# mk312lite_V4a.net
KiCad netlist of a schematic drawn in EAGLE
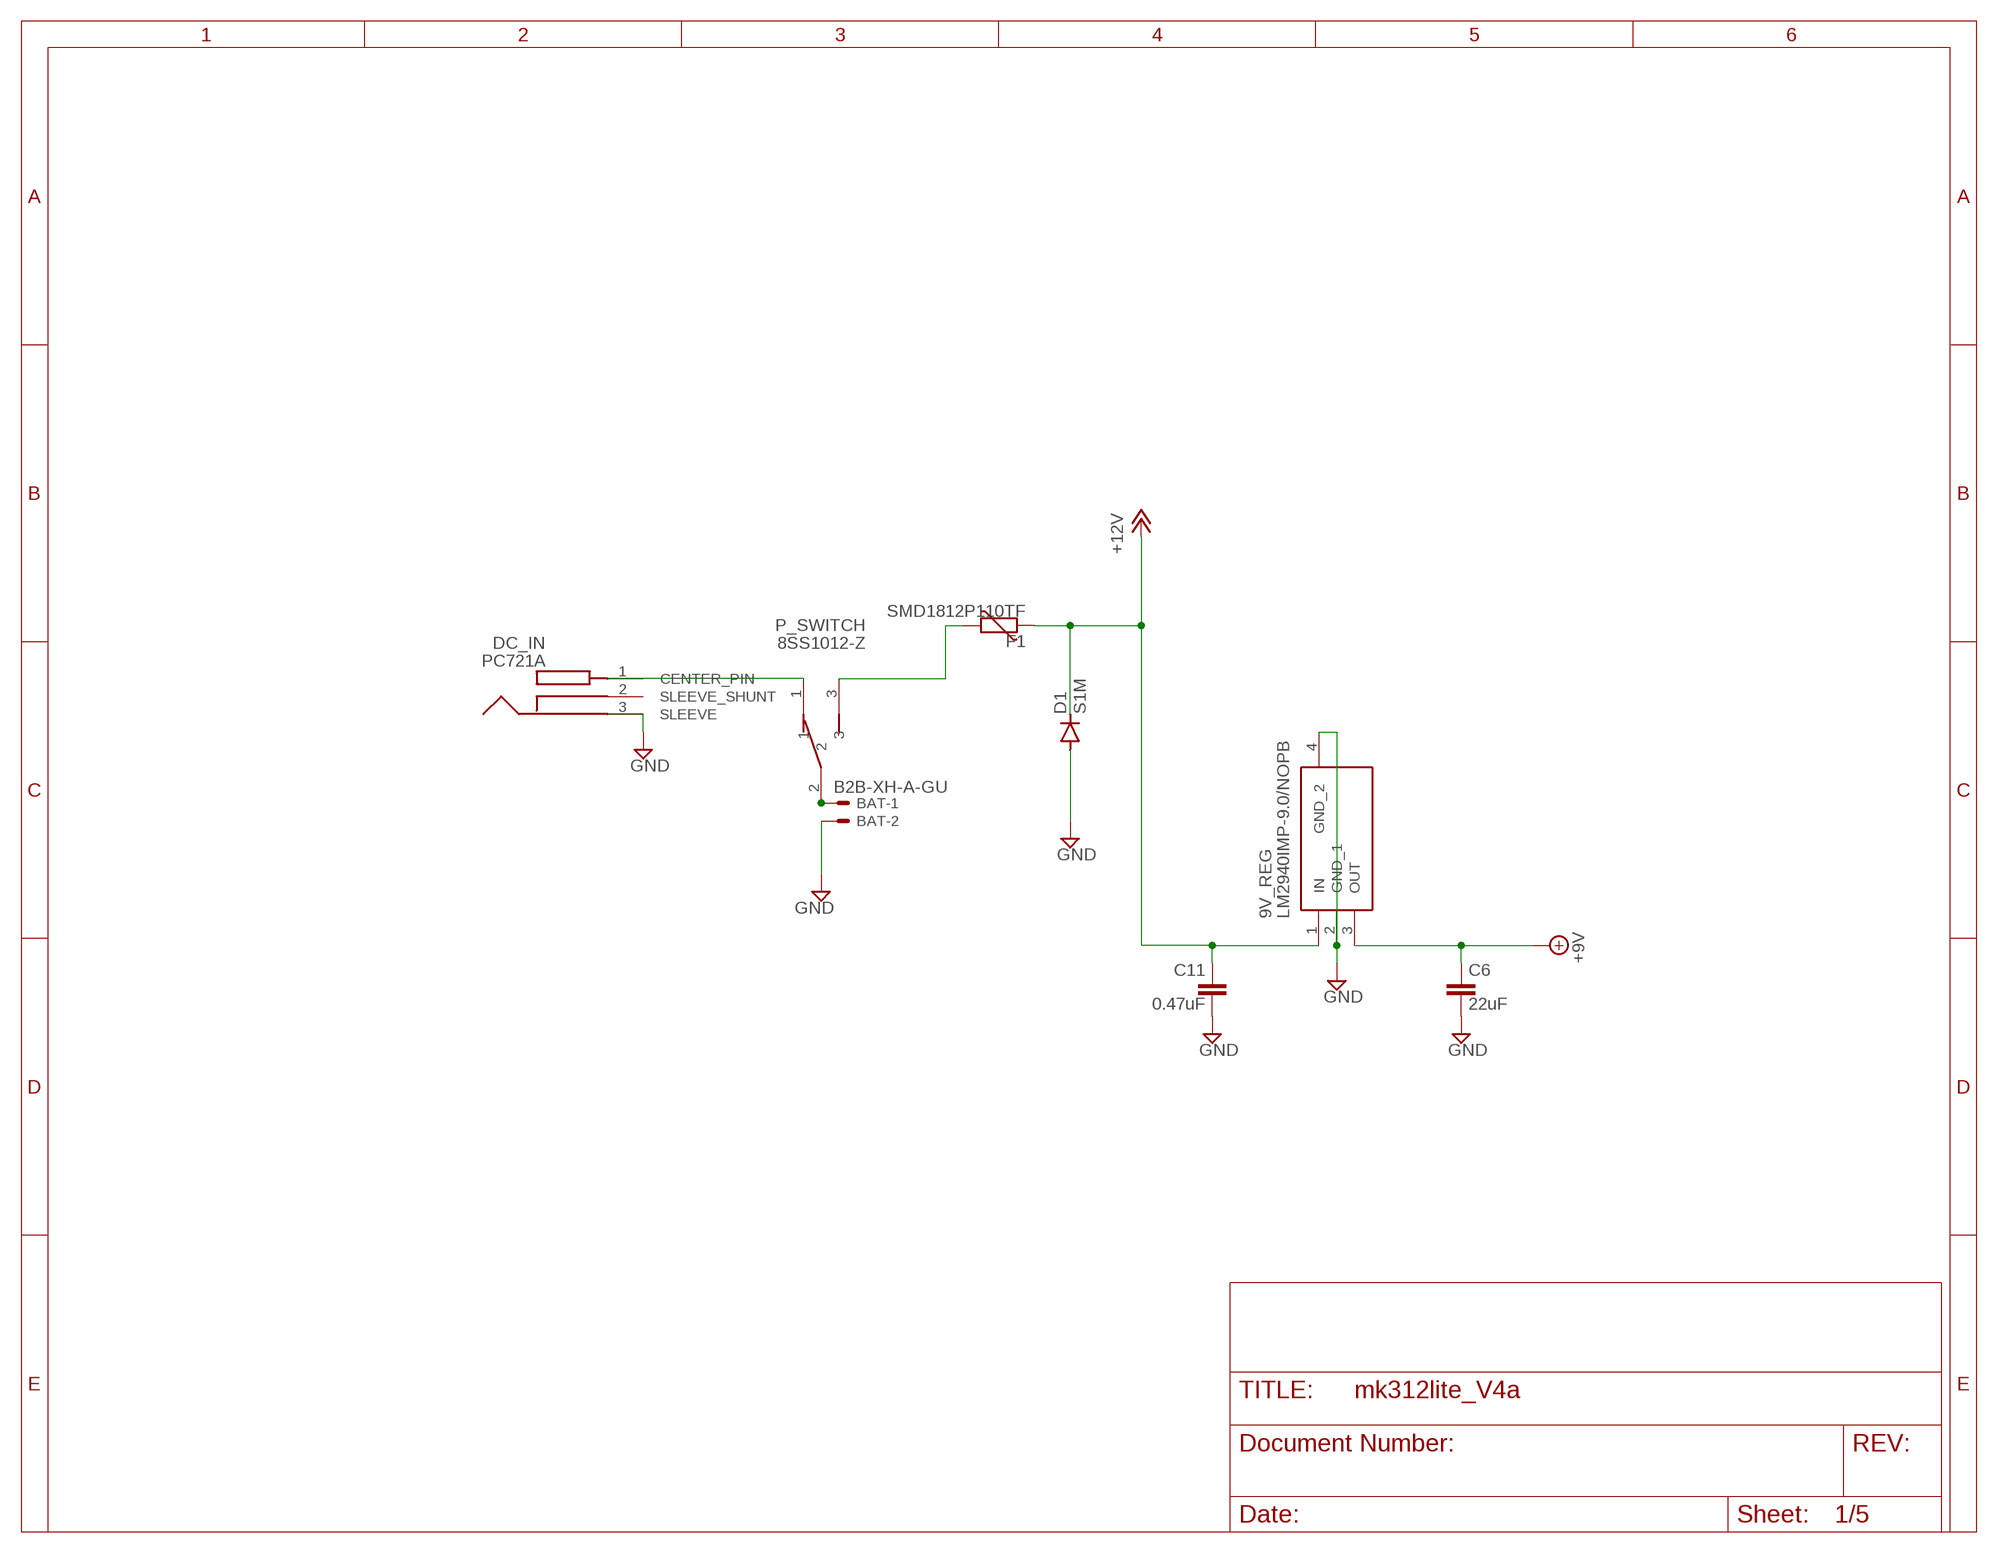
[diagram p0: schematic, sheet 1]
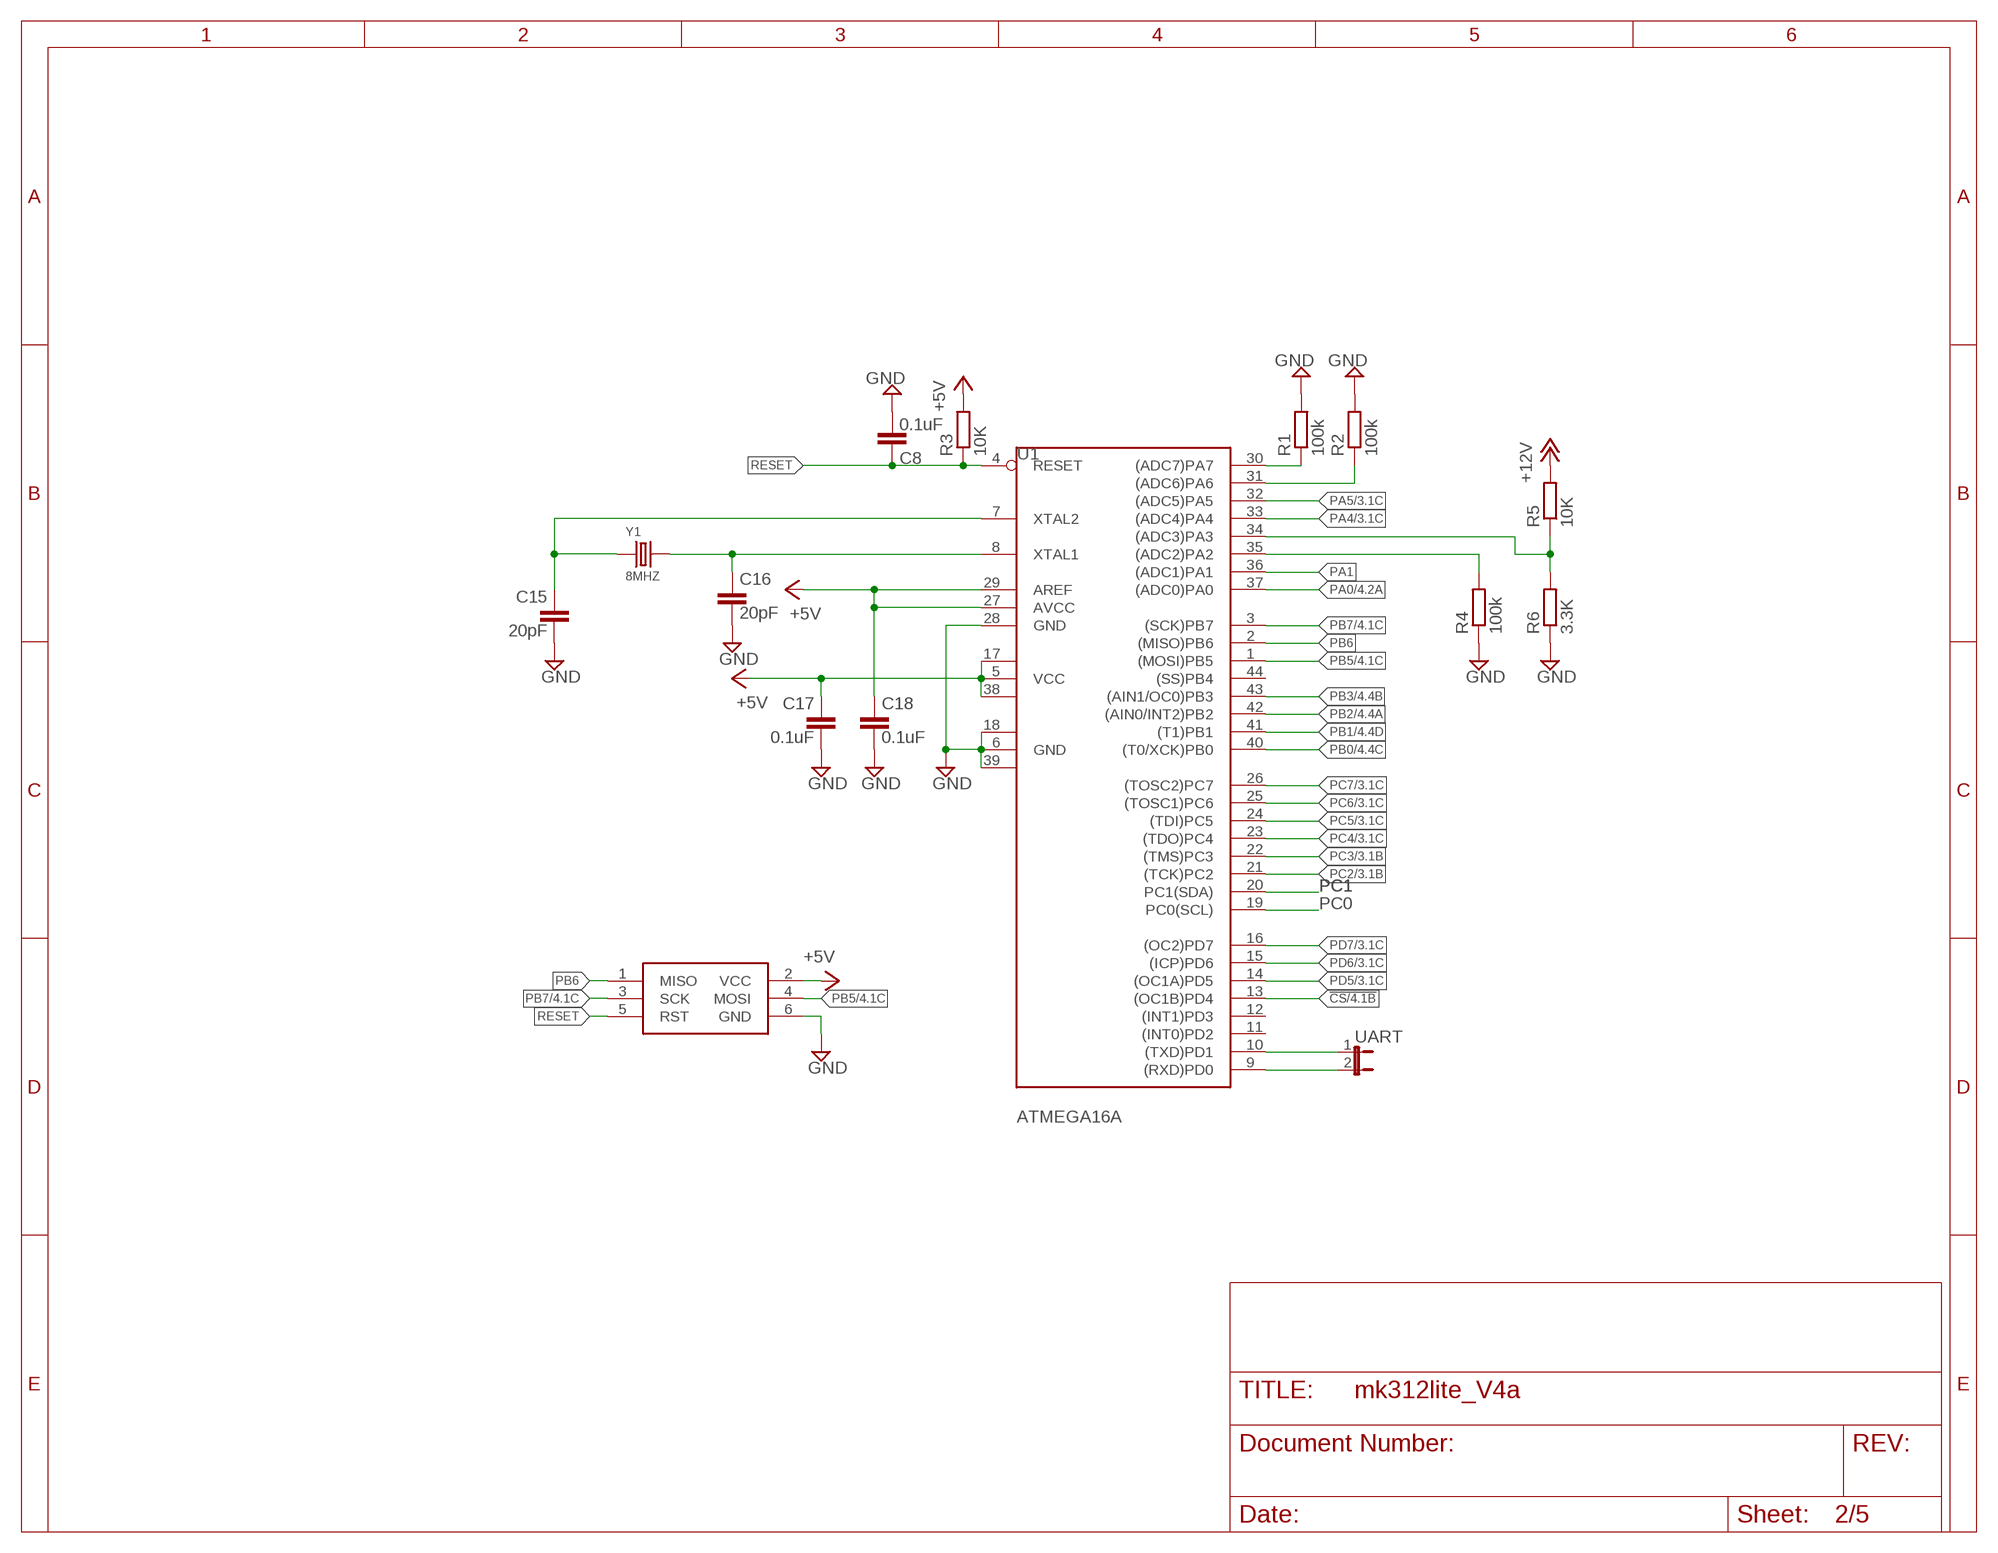
[diagram p1: schematic, sheet 2]
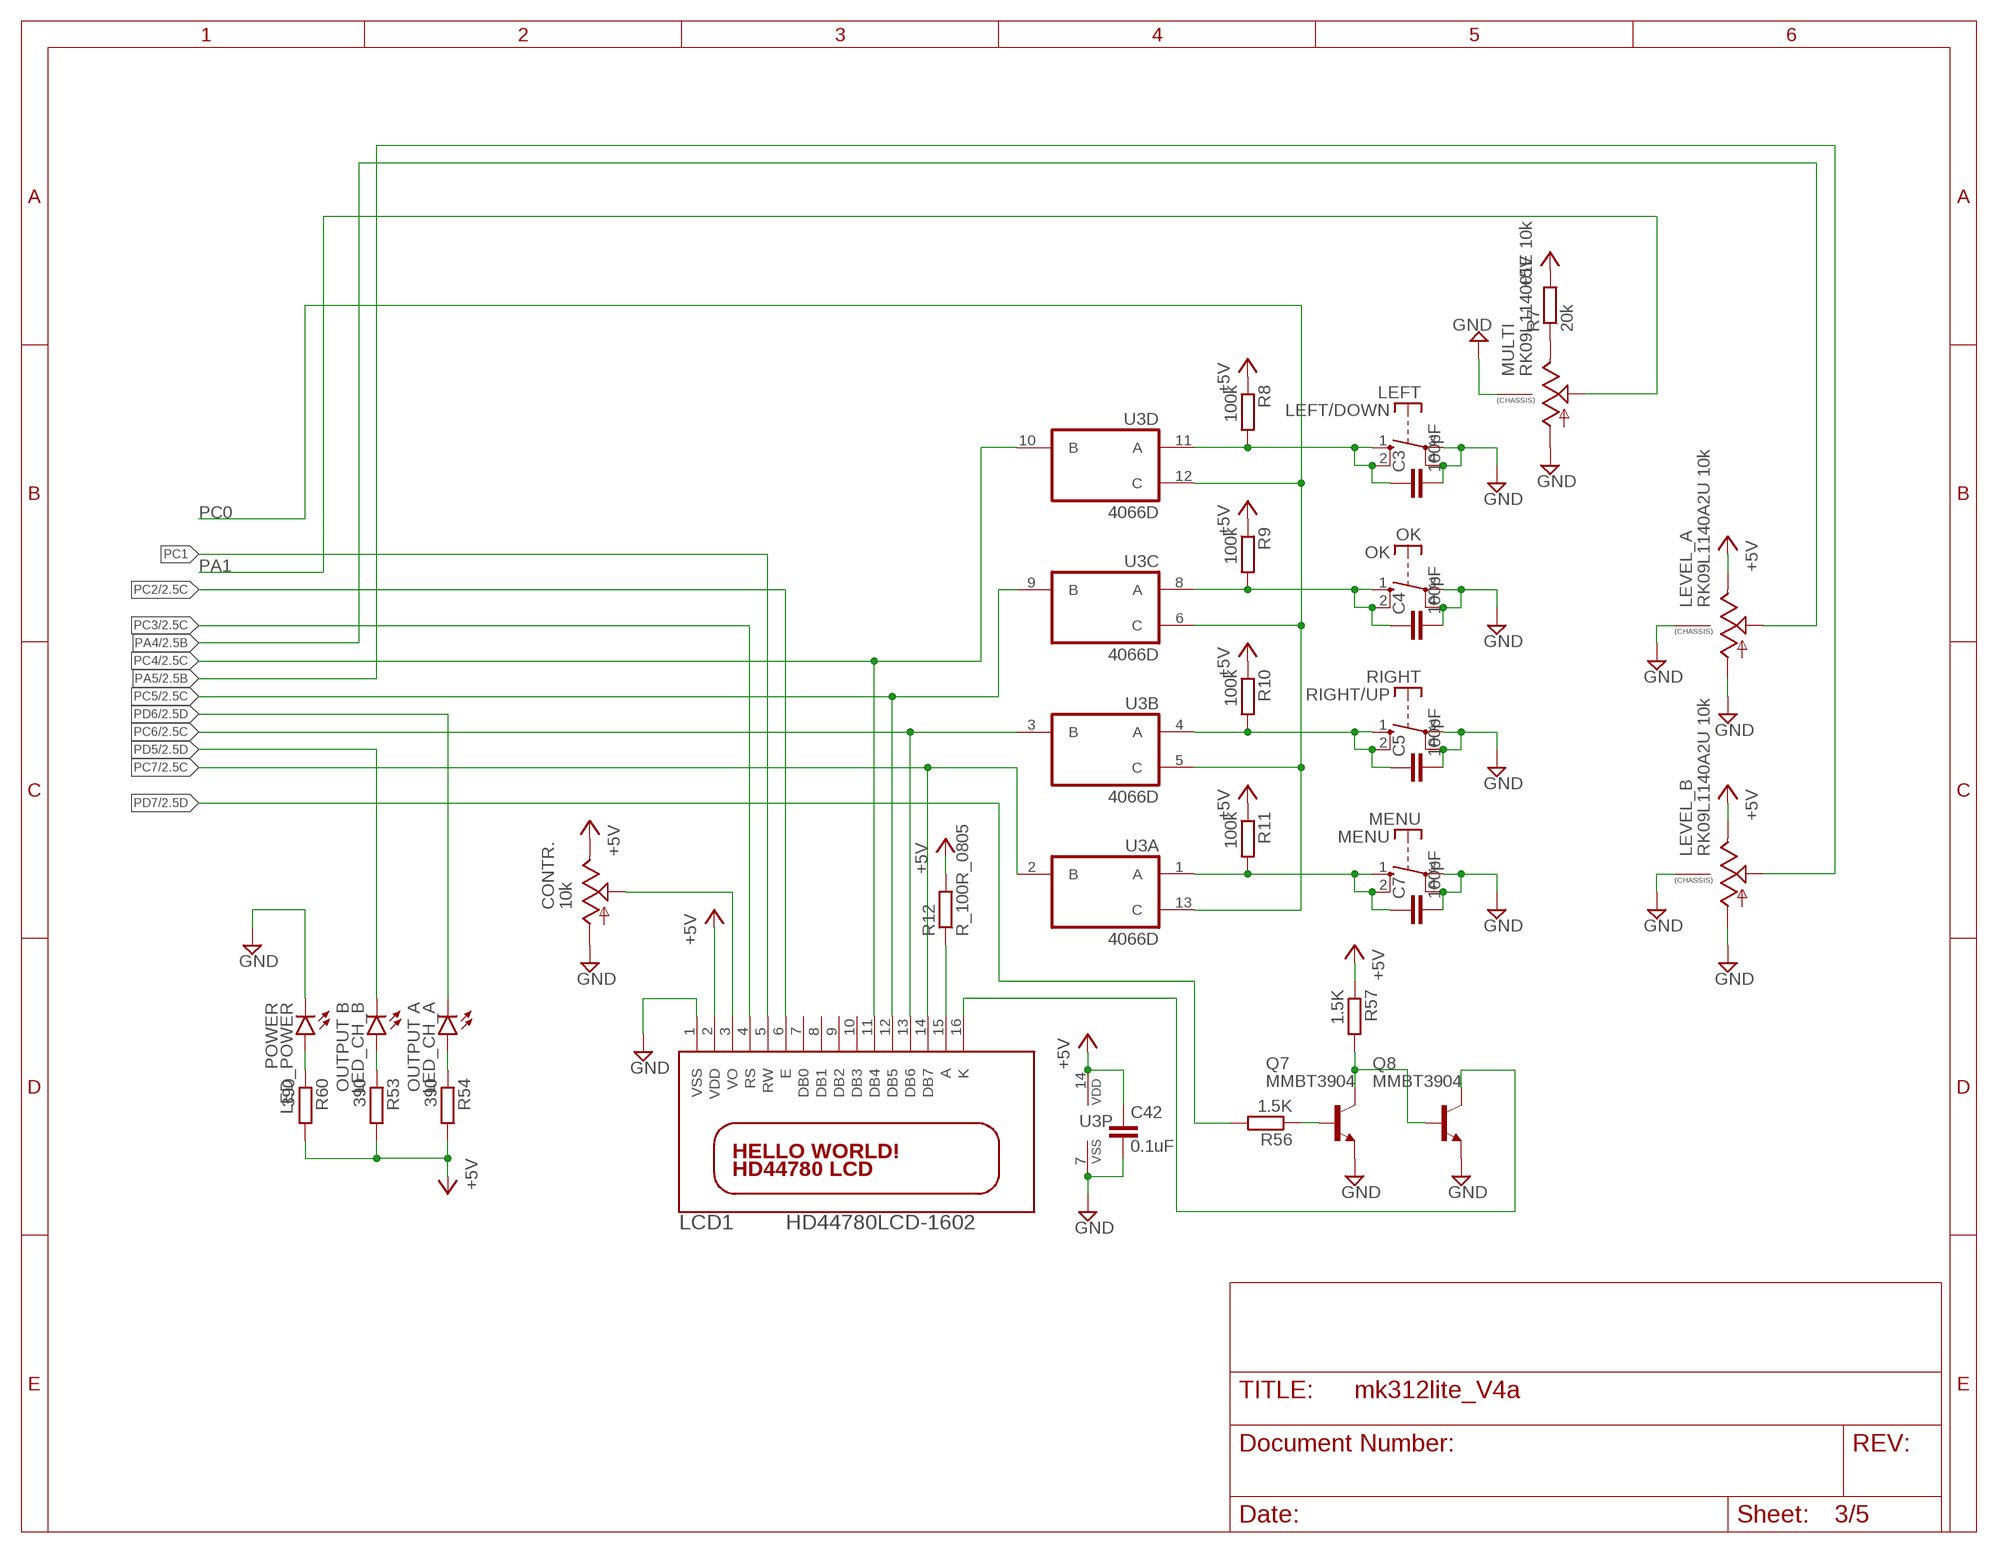
[diagram p2: schematic, sheet 3]
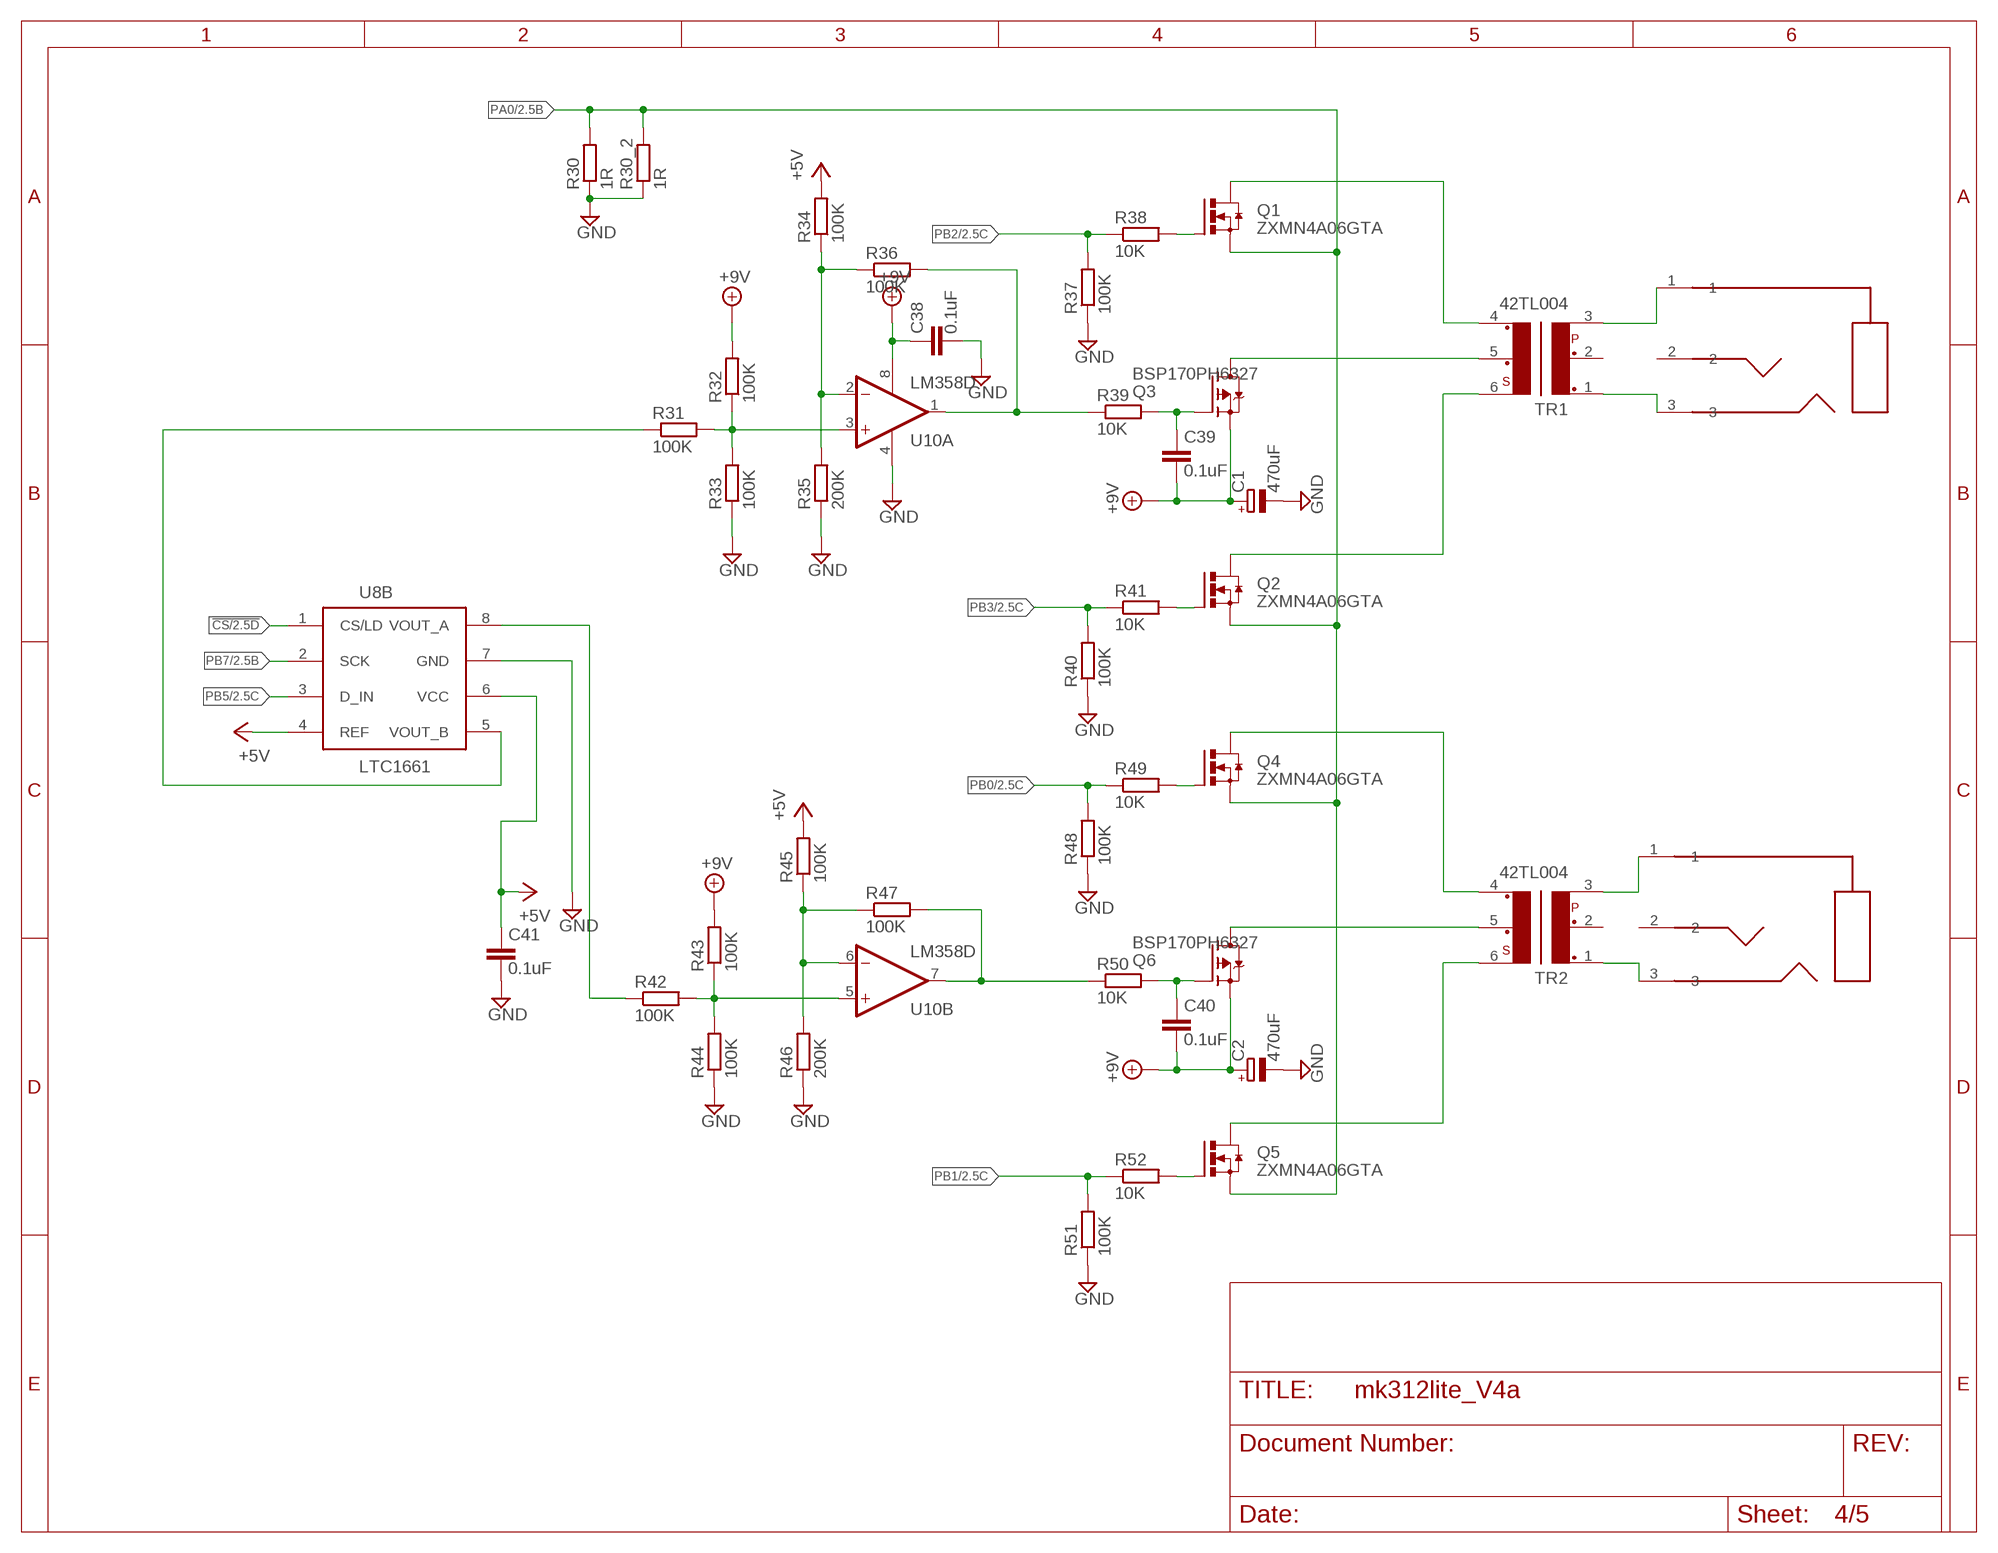
[diagram p3: schematic, sheet 4]
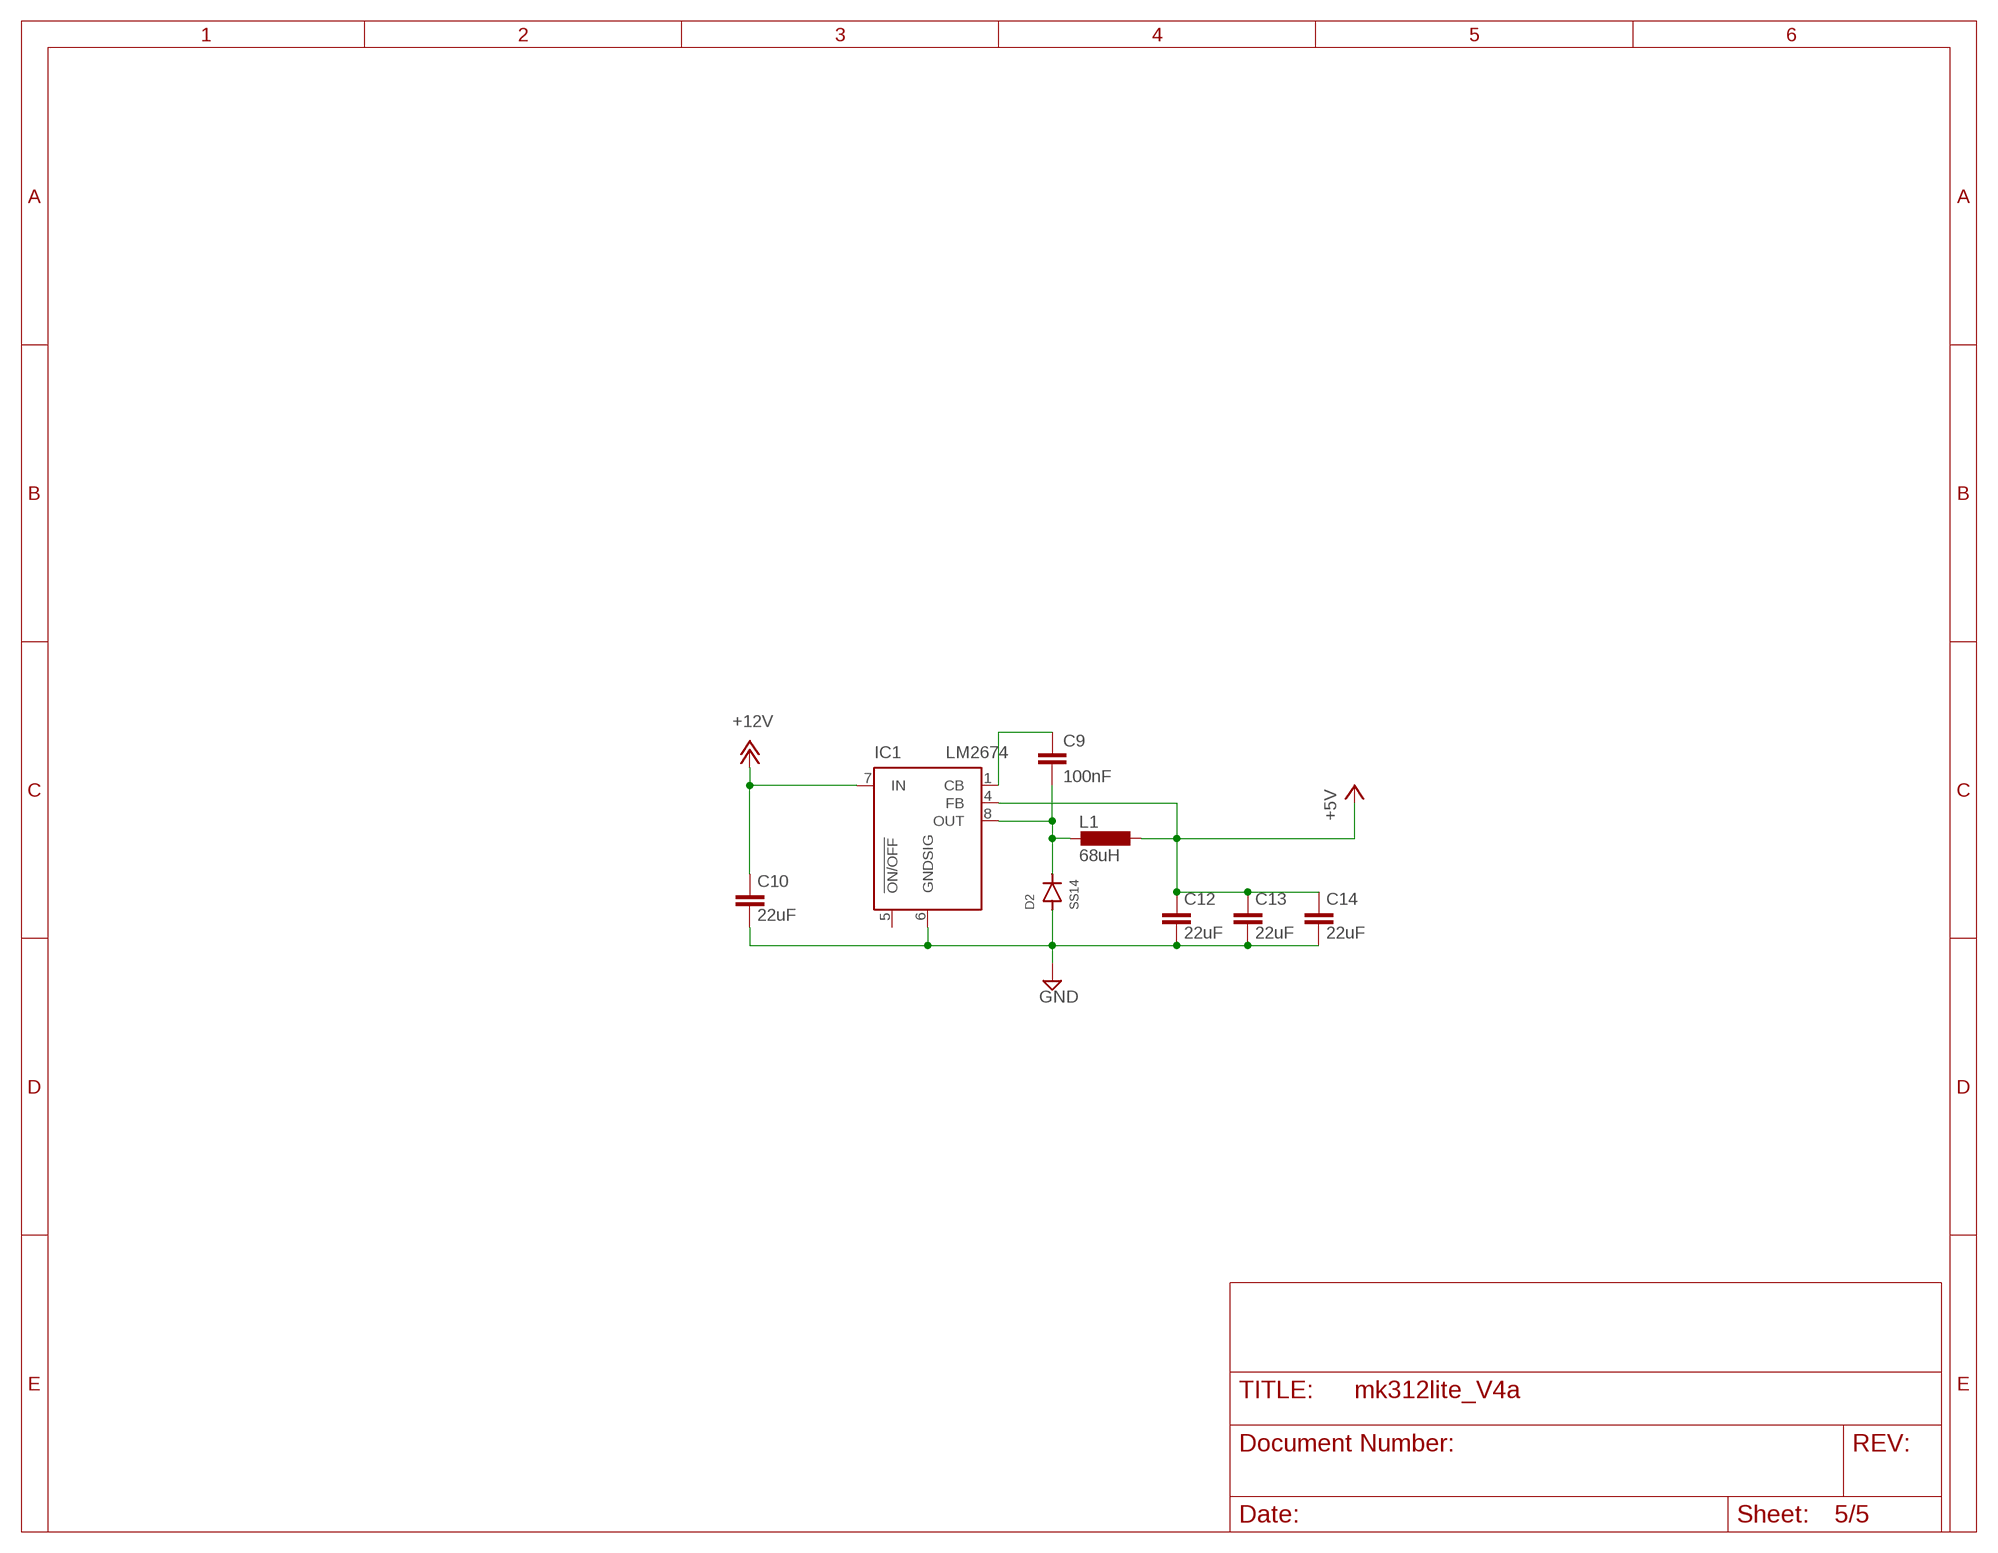
[diagram p4: schematic, sheet 5]

(export (version "E")
  (design (tool "Eeschema 10.0.6"))
  (components
    (comp (ref "C8")
      (value "0.1uF")
      (footprint "eagle-import:C0805")
      (libsource (lib "eagle-import") (part "C-EUC0805"))
    )
    (comp (ref "C15")
      (value "20pF")
      (footprint "eagle-import:C0603")
      (libsource (lib "eagle-import") (part "C-EUC0603"))
    )
    (comp (ref "C16")
      (value "20pF")
      (footprint "eagle-import:C0603")
      (libsource (lib "eagle-import") (part "C-EUC0603"))
    )
    (comp (ref "C17")
      (value "0.1uF")
      (footprint "eagle-import:C0805")
      (libsource (lib "eagle-import") (part "C-EUC0805"))
    )
    (comp (ref "C18")
      (value "0.1uF")
      (footprint "eagle-import:C0805")
      (libsource (lib "eagle-import") (part "C-EUC0805"))
    )
    (comp (ref "ISP1")
      (value "AVRISP-6")
      (footprint "eagle-import:AVRISP")
      (libsource (lib "eagle-import") (part "AVRISP-6"))
    )
    (comp (ref "R1")
      (value "100k")
      (footprint "eagle-import:R0805")
      (libsource (lib "eagle-import") (part "R-EU_R0805"))
    )
    (comp (ref "R2")
      (value "100k")
      (footprint "eagle-import:R0805")
      (libsource (lib "eagle-import") (part "R-EU_R0805"))
    )
    (comp (ref "R3")
      (value "10K")
      (footprint "eagle-import:R0805")
      (libsource (lib "eagle-import") (part "R-EU_R0805"))
    )
    (comp (ref "R4")
      (value "100k")
      (footprint "eagle-import:R0805")
      (libsource (lib "eagle-import") (part "R-EU_R0805"))
    )
    (comp (ref "R5")
      (value "10K")
      (footprint "eagle-import:R0805")
      (libsource (lib "eagle-import") (part "R-EU_R0805"))
    )
    (comp (ref "R6")
      (value "3.3K")
      (footprint "eagle-import:R0805")
      (libsource (lib "eagle-import") (part "R-EU_R0805"))
    )
    (comp (ref "U1")
      (value "ATMEGA16A")
      (footprint "eagle-import:TQFP44")
      (fields (field (name "MPN") "ATMEGA16-16AU"))
      (libsource (lib "eagle-import") (part "MEGA16-A"))
    )
    (comp (ref "UART")
      (value "JP1E")
      (footprint "eagle-import:JP1")
      (libsource (lib "eagle-import") (part "JP1E"))
    )
    (comp (ref "Y1")
      (value "8MHZ")
      (footprint "eagle-import:X2-SMD-5.0X3.2X1.3MM")
      (fields (field (name "MPN") "5032/2P"))
      (libsource (lib "eagle-import") (part "SMD-CRYSTAL-8MHZ-20PF-20PPM(2P-5.0X3.2MM)"))
    )
    (comp (ref "C1")
      (value "470uF")
      (footprint "eagle-import:150CLZ-1010")
      (libsource (lib "eagle-import") (part "CPOL-EU150CLZ-1010"))
    )
    (comp (ref "C2")
      (value "470uF")
      (footprint "eagle-import:150CLZ-1010")
      (libsource (lib "eagle-import") (part "CPOL-EU150CLZ-1010"))
    )
    (comp (ref "C38")
      (value "0.1uF")
      (footprint "eagle-import:C0805")
      (libsource (lib "eagle-import") (part "C-EUC0805"))
    )
    (comp (ref "C39")
      (value "0.1uF")
      (footprint "eagle-import:C0805")
      (libsource (lib "eagle-import") (part "C-EUC0805"))
    )
    (comp (ref "C40")
      (value "0.1uF")
      (footprint "eagle-import:C0805")
      (libsource (lib "eagle-import") (part "C-EUC0805"))
    )
    (comp (ref "C41")
      (value "0.1uF")
      (footprint "eagle-import:C0805")
      (libsource (lib "eagle-import") (part "C-EUC0805"))
    )
    (comp (ref "CHAN_A")
      (value "PJ-301C")
      (footprint "eagle-import:PJ-301C")
      (libsource (lib "eagle-import") (part "PC-301C"))
    )
    (comp (ref "CHAN_B")
      (value "PJ-301C")
      (footprint "eagle-import:PJ-301C")
      (libsource (lib "eagle-import") (part "PC-301C"))
    )
    (comp (ref "Q1")
      (value "ZXMN4A06GTA")
      (footprint "eagle-import:SOT223")
      (libsource (lib "eagle-import") (part "N-HEXFET-2D_?-SOT232IRLL2705"))
    )
    (comp (ref "Q2")
      (value "ZXMN4A06GTA")
      (footprint "eagle-import:SOT223")
      (libsource (lib "eagle-import") (part "N-HEXFET-2D_?-SOT232IRLL2705"))
    )
    (comp (ref "Q3")
      (value "BSP170PH6327")
      (footprint "eagle-import:SOT230P700X180-4N")
      (libsource (lib "eagle-import") (part "IRFL9014TRPBF"))
    )
    (comp (ref "Q4")
      (value "ZXMN4A06GTA")
      (footprint "eagle-import:SOT223")
      (libsource (lib "eagle-import") (part "N-HEXFET-2D_?-SOT232IRLL2705"))
    )
    (comp (ref "Q5")
      (value "ZXMN4A06GTA")
      (footprint "eagle-import:SOT223")
      (libsource (lib "eagle-import") (part "N-HEXFET-2D_?-SOT232IRLL2705"))
    )
    (comp (ref "Q6")
      (value "BSP170PH6327")
      (footprint "eagle-import:SOT230P700X180-4N")
      (libsource (lib "eagle-import") (part "IRFL9014TRPBF"))
    )
    (comp (ref "R30")
      (value "1R")
      (footprint "eagle-import:R1206")
      (libsource (lib "eagle-import") (part "R-EU_R1206"))
    )
    (comp (ref "R30_2")
      (value "1R")
      (footprint "eagle-import:R1206")
      (libsource (lib "eagle-import") (part "R-EU_R1206"))
    )
    (comp (ref "R31")
      (value "100K")
      (footprint "eagle-import:R0805")
      (libsource (lib "eagle-import") (part "R-EU_R0805"))
    )
    (comp (ref "R32")
      (value "100K")
      (footprint "eagle-import:R0805")
      (libsource (lib "eagle-import") (part "R-EU_R0805"))
    )
    (comp (ref "R33")
      (value "100K")
      (footprint "eagle-import:R0805")
      (libsource (lib "eagle-import") (part "R-EU_R0805"))
    )
    (comp (ref "R34")
      (value "100K")
      (footprint "eagle-import:R0805")
      (libsource (lib "eagle-import") (part "R-EU_R0805"))
    )
    (comp (ref "R35")
      (value "200K")
      (footprint "eagle-import:R0805")
      (libsource (lib "eagle-import") (part "R-EU_R0805"))
    )
    (comp (ref "R36")
      (value "100K")
      (footprint "eagle-import:R0805")
      (libsource (lib "eagle-import") (part "R-EU_R0805"))
    )
    (comp (ref "R37")
      (value "100K")
      (footprint "eagle-import:R0805")
      (libsource (lib "eagle-import") (part "R-EU_R0805"))
    )
    (comp (ref "R38")
      (value "10K")
      (footprint "eagle-import:R0805")
      (libsource (lib "eagle-import") (part "R-EU_R0805"))
    )
    (comp (ref "R39")
      (value "10K")
      (footprint "eagle-import:R0805")
      (libsource (lib "eagle-import") (part "R-EU_R0805"))
    )
    (comp (ref "R40")
      (value "100K")
      (footprint "eagle-import:R0805")
      (libsource (lib "eagle-import") (part "R-EU_R0805"))
    )
    (comp (ref "R41")
      (value "10K")
      (footprint "eagle-import:R0805")
      (libsource (lib "eagle-import") (part "R-EU_R0805"))
    )
    (comp (ref "R42")
      (value "100K")
      (footprint "eagle-import:R0805")
      (libsource (lib "eagle-import") (part "R-EU_R0805"))
    )
    (comp (ref "R43")
      (value "100K")
      (footprint "eagle-import:R0805")
      (libsource (lib "eagle-import") (part "R-EU_R0805"))
    )
    (comp (ref "R44")
      (value "100K")
      (footprint "eagle-import:R0805")
      (libsource (lib "eagle-import") (part "R-EU_R0805"))
    )
    (comp (ref "R45")
      (value "100K")
      (footprint "eagle-import:R0805")
      (libsource (lib "eagle-import") (part "R-EU_R0805"))
    )
    (comp (ref "R46")
      (value "200K")
      (footprint "eagle-import:R0805")
      (libsource (lib "eagle-import") (part "R-EU_R0805"))
    )
    (comp (ref "R47")
      (value "100K")
      (footprint "eagle-import:R0805")
      (libsource (lib "eagle-import") (part "R-EU_R0805"))
    )
    (comp (ref "R48")
      (value "100K")
      (footprint "eagle-import:R0805")
      (libsource (lib "eagle-import") (part "R-EU_R0805"))
    )
    (comp (ref "R49")
      (value "10K")
      (footprint "eagle-import:R0805")
      (libsource (lib "eagle-import") (part "R-EU_R0805"))
    )
    (comp (ref "R50")
      (value "10K")
      (footprint "eagle-import:R0805")
      (libsource (lib "eagle-import") (part "R-EU_R0805"))
    )
    (comp (ref "R51")
      (value "100K")
      (footprint "eagle-import:R0805")
      (libsource (lib "eagle-import") (part "R-EU_R0805"))
    )
    (comp (ref "R52")
      (value "10K")
      (footprint "eagle-import:R0805")
      (libsource (lib "eagle-import") (part "R-EU_R0805"))
    )
    (comp (ref "TR1")
      (value "42TL004")
      (footprint "eagle-import:42TL")
      (libsource (lib "eagle-import") (part "42T?L023"))
    )
    (comp (ref "TR2")
      (value "42TL004")
      (footprint "eagle-import:42TL")
      (libsource (lib "eagle-import") (part "42T?L023"))
    )
    (comp (ref "U8B")
      (value "LTC1661")
      (footprint "eagle-import:MSOP8")
      (libsource (lib "eagle-import") (part "LTC1661IMS8"))
    )
    (comp (ref "U10")
      (value "LM358D")
      (footprint "eagle-import:SO08")
      (libsource (lib "eagle-import") (part "LM358D"))
    )
    (comp (ref "9V_REG")
      (value "LM2940IMP-9.0/NOPB")
      (footprint "eagle-import:SOT230P700X180-4N")
      (fields (field (name "MOUSER_PART_NUMBER") "926-LM2940IMP90NOPB"))
      (libsource (lib "eagle-import") (part "LM2940IMP-9.0_NOPB"))
    )
    (comp (ref "BAT")
      (value "B2B-XH-A-GU")
      (footprint "eagle-import:JST-XH-02-PACKAGE-LONG-PAD")
      (libsource (lib "eagle-import") (part "JST-XH-02-PIN-LONG-PAD"))
    )
    (comp (ref "C6")
      (value "22uF")
      (footprint "eagle-import:C1206")
      (libsource (lib "eagle-import") (part "C-EUC1206"))
    )
    (comp (ref "C11")
      (value "0.47uF")
      (footprint "eagle-import:C0805")
      (libsource (lib "eagle-import") (part "C-EUC0805"))
    )
    (comp (ref "D1")
      (value "S1M")
      (footprint "eagle-import:SMA")
      (libsource (lib "eagle-import") (part "S1M"))
    )
    (comp (ref "DC_IN")
      (value "PC721A")
      (footprint "eagle-import:PC721A")
      (fields (field (name "MOUSER_PART_NUMBER") "502-PC721A"))
      (libsource (lib "eagle-import") (part "PC721A"))
    )
    (comp (ref "F1")
      (value "SMD1812P110TF")
      (footprint "eagle-import:CT_CN1812")
      (libsource (lib "eagle-import") (part "VARISTORCN1812"))
    )
    (comp (ref "P_SWITCH")
      (value "8SS1012-Z")
      (footprint "eagle-import:8SS1012Z")
      (libsource (lib "eagle-import") (part "8SS1012-Z"))
    )
    (comp (ref "C9")
      (value "100nF")
      (footprint "eagle-import:C0805")
      (libsource (lib "eagle-import") (part "C-EUC0805"))
    )
    (comp (ref "C10")
      (value "22uF")
      (footprint "eagle-import:C1206")
      (libsource (lib "eagle-import") (part "C-EUC1206"))
    )
    (comp (ref "C12")
      (value "22uF")
      (footprint "eagle-import:C1206")
      (libsource (lib "eagle-import") (part "C-EUC1206"))
    )
    (comp (ref "C13")
      (value "22uF")
      (footprint "eagle-import:C1206")
      (libsource (lib "eagle-import") (part "C-EUC1206"))
    )
    (comp (ref "C14")
      (value "22uF")
      (footprint "eagle-import:C1206")
      (libsource (lib "eagle-import") (part "C-EUC1206"))
    )
    (comp (ref "D2")
      (value "SS14")
      (footprint "eagle-import:SMA")
      (libsource (lib "eagle-import") (part "S1M"))
    )
    (comp (ref "IC1")
      (value "LM2674")
      (footprint "eagle-import:SO08")
      (libsource (lib "eagle-import") (part "LM2674"))
    )
    (comp (ref "L1")
      (value "68uH")
      (footprint "eagle-import:SMNR4030-151MT")
      (libsource (lib "eagle-import") (part "SMNR4030-151MT"))
    )
    (comp (ref "C3")
      (value "100pF")
      (footprint "eagle-import:C0805")
      (libsource (lib "eagle-import") (part "C-EUC0805"))
    )
    (comp (ref "C4")
      (value "100pF")
      (footprint "eagle-import:C0805")
      (libsource (lib "eagle-import") (part "C-EUC0805"))
    )
    (comp (ref "C5")
      (value "100pF")
      (footprint "eagle-import:C0805")
      (libsource (lib "eagle-import") (part "C-EUC0805"))
    )
    (comp (ref "C7")
      (value "100pF")
      (footprint "eagle-import:C0805")
      (libsource (lib "eagle-import") (part "C-EUC0805"))
    )
    (comp (ref "C42")
      (value "0.1uF")
      (footprint "eagle-import:C0805")
      (libsource (lib "eagle-import") (part "C-EUC0805"))
    )
    (comp (ref "CONTR.")
      (value "10k")
      (footprint "eagle-import:B25P")
      (libsource (lib "eagle-import") (part "TRIM_US-B25P"))
    )
    (comp (ref "LCD1")
      (value "HD44780LCD-1602")
      (footprint "eagle-import:LCD1602")
      (libsource (lib "eagle-import") (part "HD44780LCD-1602"))
    )
    (comp (ref "LED_CH_A")
      (value "OUTPUT A")
      (footprint "eagle-import:LED3MM")
      (libsource (lib "eagle-import") (part "LED3MM"))
    )
    (comp (ref "LED_CH_B")
      (value "OUTPUT B")
      (footprint "eagle-import:LED3MM")
      (libsource (lib "eagle-import") (part "LED3MM"))
    )
    (comp (ref "LED_POWER")
      (value "POWER")
      (footprint "eagle-import:LED3MM")
      (libsource (lib "eagle-import") (part "LED3MM"))
    )
    (comp (ref "LEFT")
      (value "LEFT/DOWN")
      (footprint "eagle-import:DTE6K")
      (libsource (lib "eagle-import") (part "DTE6K"))
    )
    (comp (ref "LEVEL_A")
      (value "RK09L1140A2U 10k")
      (footprint "eagle-import:9MM_SNAP-IN_POT")
      (libsource (lib "eagle-import") (part "9MM_SNAP-IN_POT_CHASSIS"))
    )
    (comp (ref "LEVEL_B")
      (value "RK09L1140A2U 10k")
      (footprint "eagle-import:9MM_SNAP-IN_POT")
      (libsource (lib "eagle-import") (part "9MM_SNAP-IN_POT_CHASSIS"))
    )
    (comp (ref "MENU")
      (value "MENU")
      (footprint "eagle-import:DTE6K")
      (libsource (lib "eagle-import") (part "DTE6K"))
    )
    (comp (ref "MULTI")
      (value "RK09L114001E 10k")
      (footprint "eagle-import:9MM_SNAP-IN_POT")
      (libsource (lib "eagle-import") (part "9MM_SNAP-IN_POT_CHASSIS"))
    )
    (comp (ref "OK")
      (value "OK")
      (footprint "eagle-import:DTE6K")
      (libsource (lib "eagle-import") (part "DTE6K"))
    )
    (comp (ref "Q7")
      (value "MMBT3904")
      (footprint "eagle-import:SOT23-BEC")
      (libsource (lib "eagle-import") (part "-NPN-SOT23-BECMMBT3904LT1"))
    )
    (comp (ref "Q8")
      (value "MMBT3904")
      (footprint "eagle-import:SOT23-BEC")
      (libsource (lib "eagle-import") (part "-NPN-SOT23-BECMMBT3904LT1"))
    )
    (comp (ref "R7")
      (value "20k")
      (footprint "eagle-import:R0805")
      (libsource (lib "eagle-import") (part "R-EU_R0805"))
    )
    (comp (ref "R8")
      (value "100k")
      (footprint "eagle-import:R0805")
      (libsource (lib "eagle-import") (part "R-EU_R0805"))
    )
    (comp (ref "R9")
      (value "100k")
      (footprint "eagle-import:R0805")
      (libsource (lib "eagle-import") (part "R-EU_R0805"))
    )
    (comp (ref "R10")
      (value "100k")
      (footprint "eagle-import:R0805")
      (libsource (lib "eagle-import") (part "R-EU_R0805"))
    )
    (comp (ref "R11")
      (value "100k")
      (footprint "eagle-import:R0805")
      (libsource (lib "eagle-import") (part "R-EU_R0805"))
    )
    (comp (ref "R12")
      (value "R_100R_0805")
      (footprint "eagle-import:R0805")
      (fields (field (name "LCSC_PART") "C17408"))
      (libsource (lib "eagle-import") (part "R__0805100R"))
    )
    (comp (ref "R53")
      (value "390")
      (footprint "eagle-import:R0805")
      (libsource (lib "eagle-import") (part "R-EU_R0805"))
    )
    (comp (ref "R54")
      (value "390")
      (footprint "eagle-import:R0805")
      (libsource (lib "eagle-import") (part "R-EU_R0805"))
    )
    (comp (ref "R56")
      (value "1.5K")
      (footprint "eagle-import:R0805")
      (libsource (lib "eagle-import") (part "R-EU_R0805"))
    )
    (comp (ref "R57")
      (value "1.5K")
      (footprint "eagle-import:R0805")
      (libsource (lib "eagle-import") (part "R-EU_R0805"))
    )
    (comp (ref "R60")
      (value "390")
      (footprint "eagle-import:R0805")
      (libsource (lib "eagle-import") (part "R-EU_R0805"))
    )
    (comp (ref "RIGHT")
      (value "RIGHT/UP")
      (footprint "eagle-import:DTE6K")
      (libsource (lib "eagle-import") (part "DTE6K"))
    )
    (comp (ref "U3")
      (value "4066D")
      (footprint "eagle-import:SO14")
      (libsource (lib "eagle-import") (part "4066D"))
    )
  )
  (nets
    (net (code "1") (name "+5V") (class "Default")
      (node (ref "C12") (pin "1") (pinfunction "1_1") (pintype "passive"))
      (node (ref "C13") (pin "1") (pinfunction "1_1") (pintype "passive"))
      (node (ref "C14") (pin "1") (pinfunction "1_1") (pintype "passive"))
      (node (ref "C17") (pin "1") (pinfunction "1_1") (pintype "passive"))
      (node (ref "C18") (pin "1") (pinfunction "1_1") (pintype "passive"))
      (node (ref "C41") (pin "1") (pinfunction "1_1") (pintype "passive"))
      (node (ref "C42") (pin "1") (pinfunction "1_1") (pintype "passive"))
      (node (ref "CONTR.") (pin "E") (pinfunction "E_E") (pintype "passive"))
      (node (ref "IC1") (pin "4") (pinfunction "FB_4") (pintype "input"))
      (node (ref "ISP1") (pin "2") (pinfunction "VCC_2") (pintype "power_in"))
      (node (ref "L1") (pin "2") (pinfunction "2_2") (pintype "passive"))
      (node (ref "LCD1") (pin "2") (pinfunction "VDD_2") (pintype "power_in"))
      (node (ref "LEVEL_A") (pin "3") (pinfunction "E_3") (pintype "passive"))
      (node (ref "LEVEL_B") (pin "3") (pinfunction "E_3") (pintype "passive"))
      (node (ref "R10") (pin "1") (pinfunction "1_1") (pintype "passive"))
      (node (ref "R11") (pin "1") (pinfunction "1_1") (pintype "passive"))
      (node (ref "R12") (pin "2") (pinfunction "2_2") (pintype "passive"))
      (node (ref "R3") (pin "2") (pinfunction "2_2") (pintype "passive"))
      (node (ref "R34") (pin "2") (pinfunction "2_2") (pintype "passive"))
      (node (ref "R45") (pin "2") (pinfunction "2_2") (pintype "passive"))
      (node (ref "R53") (pin "2") (pinfunction "2_2") (pintype "passive"))
      (node (ref "R54") (pin "2") (pinfunction "2_2") (pintype "passive"))
      (node (ref "R57") (pin "1") (pinfunction "1_1") (pintype "passive"))
      (node (ref "R60") (pin "2") (pinfunction "2_2") (pintype "passive"))
      (node (ref "R7") (pin "2") (pinfunction "2_2") (pintype "passive"))
      (node (ref "R8") (pin "1") (pinfunction "1_1") (pintype "passive"))
      (node (ref "R9") (pin "1") (pinfunction "1_1") (pintype "passive"))
      (node (ref "U1") (pin "17") (pinfunction "VCC1_17") (pintype "power_in"))
      (node (ref "U1") (pin "27") (pinfunction "AVCC_27") (pintype "power_in"))
      (node (ref "U1") (pin "29") (pinfunction "AREF_29") (pintype "passive"))
      (node (ref "U1") (pin "38") (pinfunction "VCC2_38") (pintype "power_in"))
      (node (ref "U1") (pin "5") (pinfunction "VCC_5") (pintype "power_in"))
      (node (ref "U3") (pin "14") (pinfunction "VDD_14") (pintype "power_in"))
      (node (ref "U8B") (pin "4") (pinfunction "REF_4") (pintype "input"))
      (node (ref "U8B") (pin "6") (pinfunction "VCC_6") (pintype "power_in"))
    )
    (net (code "2") (name "+9V") (class "Default")
      (node (ref "9V_REG") (pin "3") (pinfunction "OUT_3") (pintype "bidirectional"))
      (node (ref "C1") (pin "+") (pinfunction "+_+") (pintype "passive"))
      (node (ref "C2") (pin "+") (pinfunction "+_+") (pintype "passive"))
      (node (ref "C38") (pin "1") (pinfunction "1_1") (pintype "passive"))
      (node (ref "C39") (pin "2") (pinfunction "2_2") (pintype "passive"))
      (node (ref "C40") (pin "2") (pinfunction "2_2") (pintype "passive"))
      (node (ref "C6") (pin "1") (pinfunction "1_1") (pintype "passive"))
      (node (ref "Q3") (pin "3") (pinfunction "S_3") (pintype "passive"))
      (node (ref "Q6") (pin "3") (pinfunction "S_3") (pintype "passive"))
      (node (ref "R32") (pin "2") (pinfunction "2_2") (pintype "passive"))
      (node (ref "R43") (pin "2") (pinfunction "2_2") (pintype "passive"))
      (node (ref "U10") (pin "8") (pinfunction "V+_8") (pintype "power_in"))
    )
    (net (code "3") (name "+12V") (class "Default")
      (node (ref "9V_REG") (pin "1") (pinfunction "IN_1") (pintype "bidirectional"))
      (node (ref "C10") (pin "1") (pinfunction "1_1") (pintype "passive"))
      (node (ref "C11") (pin "1") (pinfunction "1_1") (pintype "passive"))
      (node (ref "D1") (pin "C") (pinfunction "C_C") (pintype "passive"))
      (node (ref "F1") (pin "2") (pinfunction "2_2") (pintype "passive"))
      (node (ref "IC1") (pin "7") (pinfunction "IN_7") (pintype "input"))
      (node (ref "R5") (pin "2") (pinfunction "2_2") (pintype "passive"))
    )
    (net (code "4") (name "GND") (class "Default")
      (node (ref "9V_REG") (pin "2") (pinfunction "GND_1_2") (pintype "bidirectional"))
      (node (ref "9V_REG") (pin "4") (pinfunction "GND_2_4") (pintype "bidirectional"))
      (node (ref "BAT") (pin "2") (pinfunction "S_2") (pintype "passive"))
      (node (ref "C1") (pin "-") (pinfunction "-_-") (pintype "passive"))
      (node (ref "C10") (pin "2") (pinfunction "2_2") (pintype "passive"))
      (node (ref "C11") (pin "2") (pinfunction "2_2") (pintype "passive"))
      (node (ref "C12") (pin "2") (pinfunction "2_2") (pintype "passive"))
      (node (ref "C13") (pin "2") (pinfunction "2_2") (pintype "passive"))
      (node (ref "C14") (pin "2") (pinfunction "2_2") (pintype "passive"))
      (node (ref "C15") (pin "2") (pinfunction "2_2") (pintype "passive"))
      (node (ref "C16") (pin "2") (pinfunction "2_2") (pintype "passive"))
      (node (ref "C17") (pin "2") (pinfunction "2_2") (pintype "passive"))
      (node (ref "C18") (pin "2") (pinfunction "2_2") (pintype "passive"))
      (node (ref "C2") (pin "-") (pinfunction "-_-") (pintype "passive"))
      (node (ref "C3") (pin "2") (pinfunction "2_2") (pintype "passive"))
      (node (ref "C38") (pin "2") (pinfunction "2_2") (pintype "passive"))
      (node (ref "C4") (pin "2") (pinfunction "2_2") (pintype "passive"))
      (node (ref "C41") (pin "2") (pinfunction "2_2") (pintype "passive"))
      (node (ref "C42") (pin "2") (pinfunction "2_2") (pintype "passive"))
      (node (ref "C5") (pin "2") (pinfunction "2_2") (pintype "passive"))
      (node (ref "C6") (pin "2") (pinfunction "2_2") (pintype "passive"))
      (node (ref "C7") (pin "2") (pinfunction "2_2") (pintype "passive"))
      (node (ref "C8") (pin "2") (pinfunction "2_2") (pintype "passive"))
      (node (ref "CONTR.") (pin "A") (pinfunction "A_A") (pintype "passive"))
      (node (ref "D1") (pin "A") (pinfunction "A_A") (pintype "passive"))
      (node (ref "D2") (pin "A") (pinfunction "A_A") (pintype "passive"))
      (node (ref "DC_IN") (pin "3") (pinfunction "SLEEVE_3") (pintype "bidirectional"))
      (node (ref "IC1") (pin "6") (pinfunction "GNDSIG_6") (pintype "input"))
      (node (ref "ISP1") (pin "6") (pinfunction "GND_6") (pintype "power_in"))
      (node (ref "LCD1") (pin "1") (pinfunction "VSS_1") (pintype "power_in"))
      (node (ref "LED_POWER") (pin "K") (pinfunction "C_K") (pintype "passive"))
      (node (ref "LEFT") (pin "3") (pinfunction "P_3") (pintype "passive"))
      (node (ref "LEFT") (pin "4") (pinfunction "P_4") (pintype "passive"))
      (node (ref "LEVEL_A") (pin "1") (pinfunction "A_1") (pintype "passive"))
      (node (ref "LEVEL_A") (pin "CHASSIS2") (pinfunction "P$1_CHASSIS2") (pintype "passive"))
      (node (ref "LEVEL_B") (pin "1") (pinfunction "A_1") (pintype "passive"))
      (node (ref "LEVEL_B") (pin "CHASSIS2") (pinfunction "P$1_CHASSIS2") (pintype "passive"))
      (node (ref "MENU") (pin "3") (pinfunction "P_3") (pintype "passive"))
      (node (ref "MENU") (pin "4") (pinfunction "P_4") (pintype "passive"))
      (node (ref "MULTI") (pin "1") (pinfunction "A_1") (pintype "passive"))
      (node (ref "MULTI") (pin "CHASSIS2") (pinfunction "P$1_CHASSIS2") (pintype "passive"))
      (node (ref "OK") (pin "3") (pinfunction "P_3") (pintype "passive"))
      (node (ref "OK") (pin "4") (pinfunction "P_4") (pintype "passive"))
      (node (ref "Q7") (pin "E") (pinfunction "E_E") (pintype "passive"))
      (node (ref "Q8") (pin "E") (pinfunction "E_E") (pintype "passive"))
      (node (ref "R1") (pin "2") (pinfunction "2_2") (pintype "passive"))
      (node (ref "R2") (pin "2") (pinfunction "2_2") (pintype "passive"))
      (node (ref "R30") (pin "1") (pinfunction "1_1") (pintype "passive"))
      (node (ref "R30_2") (pin "1") (pinfunction "1_1") (pintype "passive"))
      (node (ref "R33") (pin "1") (pinfunction "1_1") (pintype "passive"))
      (node (ref "R35") (pin "1") (pinfunction "1_1") (pintype "passive"))
      (node (ref "R37") (pin "1") (pinfunction "1_1") (pintype "passive"))
      (node (ref "R4") (pin "1") (pinfunction "1_1") (pintype "passive"))
      (node (ref "R40") (pin "1") (pinfunction "1_1") (pintype "passive"))
      (node (ref "R44") (pin "1") (pinfunction "1_1") (pintype "passive"))
      (node (ref "R46") (pin "1") (pinfunction "1_1") (pintype "passive"))
      (node (ref "R48") (pin "1") (pinfunction "1_1") (pintype "passive"))
      (node (ref "R51") (pin "1") (pinfunction "1_1") (pintype "passive"))
      (node (ref "R6") (pin "1") (pinfunction "1_1") (pintype "passive"))
      (node (ref "RIGHT") (pin "3") (pinfunction "P_3") (pintype "passive"))
      (node (ref "RIGHT") (pin "4") (pinfunction "P_4") (pintype "passive"))
      (node (ref "U1") (pin "18") (pinfunction "GND1_18") (pintype "power_in"))
      (node (ref "U1") (pin "28") (pinfunction "GND_28") (pintype "power_in"))
      (node (ref "U1") (pin "39") (pinfunction "GND2_39") (pintype "power_in"))
      (node (ref "U1") (pin "6") (pinfunction "GND_6") (pintype "power_in"))
      (node (ref "U10") (pin "4") (pinfunction "V-_4") (pintype "power_in"))
      (node (ref "U3") (pin "7") (pinfunction "VSS_7") (pintype "power_in"))
      (node (ref "U8B") (pin "7") (pinfunction "GND_7") (pintype "power_in"))
    )
    (net (code "5") (name "Net-(BATA-S)") (class "Default")
      (node (ref "BAT") (pin "1") (pinfunction "S_1") (pintype "passive"))
      (node (ref "P_SWITCH") (pin "2") (pinfunction "2_2") (pintype "bidirectional"))
    )
    (net (code "6") (name "Net-(CHAN_A-Pad1)") (class "Default")
      (node (ref "CHAN_A") (pin "1") (pinfunction "1_1") (pintype "bidirectional"))
      (node (ref "TR1") (pin "3") (pinfunction "3_3") (pintype "passive"))
    )
    (net (code "7") (name "Net-(CHAN_A-Pad3)") (class "Default")
      (node (ref "CHAN_A") (pin "3") (pinfunction "3_3") (pintype "bidirectional"))
      (node (ref "TR1") (pin "1") (pinfunction "1_1") (pintype "passive"))
    )
    (net (code "8") (name "Net-(CHAN_B-Pad1)") (class "Default")
      (node (ref "CHAN_B") (pin "1") (pinfunction "1_1") (pintype "bidirectional"))
      (node (ref "TR2") (pin "3") (pinfunction "3_3") (pintype "passive"))
    )
    (net (code "9") (name "Net-(CHAN_B-Pad3)") (class "Default")
      (node (ref "CHAN_B") (pin "3") (pinfunction "3_3") (pintype "bidirectional"))
      (node (ref "TR2") (pin "1") (pinfunction "1_1") (pintype "passive"))
    )
    (net (code "10") (name "Net-(DC_IN-CENTER_PIN)") (class "Default")
      (node (ref "DC_IN") (pin "1") (pinfunction "CENTER_PIN_1") (pintype "bidirectional"))
      (node (ref "P_SWITCH") (pin "1") (pinfunction "1_1") (pintype "bidirectional"))
    )
    (net (code "11") (name "Net-(F1-Pad1)") (class "Default")
      (node (ref "F1") (pin "1") (pinfunction "1_1") (pintype "passive"))
      (node (ref "P_SWITCH") (pin "3") (pinfunction "3_3") (pintype "bidirectional"))
    )
    (net (code "12") (name "Net-(IC1-CB)") (class "Default")
      (node (ref "C9") (pin "1") (pinfunction "1_1") (pintype "passive"))
      (node (ref "IC1") (pin "1") (pinfunction "CB_1") (pintype "input"))
    )
    (net (code "13") (name "Net-(IC1-OUT)") (class "Default")
      (node (ref "C9") (pin "2") (pinfunction "2_2") (pintype "passive"))
      (node (ref "D2") (pin "C") (pinfunction "C_C") (pintype "passive"))
      (node (ref "IC1") (pin "8") (pinfunction "OUT_8") (pintype "passive"))
      (node (ref "L1") (pin "1") (pinfunction "1_1") (pintype "passive"))
    )
    (net (code "14") (name "Net-(LCD1-A)") (class "Default")
      (node (ref "LCD1") (pin "15") (pinfunction "A_15") (pintype "input"))
      (node (ref "R12") (pin "1") (pinfunction "1_1") (pintype "passive"))
    )
    (net (code "15") (name "Net-(LCD1-K)") (class "Default")
      (node (ref "LCD1") (pin "16") (pinfunction "K_16") (pintype "input"))
      (node (ref "Q8") (pin "C") (pinfunction "C_C") (pintype "passive"))
    )
    (net (code "16") (name "Net-(LCD1-VO)") (class "Default")
      (node (ref "CONTR.") (pin "S") (pinfunction "S_S") (pintype "passive"))
      (node (ref "LCD1") (pin "3") (pinfunction "VO_3") (pintype "input"))
    )
    (net (code "17") (name "Net-(LED_CH_A-PadA)") (class "Default")
      (node (ref "LED_CH_A") (pin "A") (pinfunction "A_A") (pintype "passive"))
      (node (ref "R54") (pin "1") (pinfunction "1_1") (pintype "passive"))
    )
    (net (code "18") (name "Net-(LED_CH_B-PadA)") (class "Default")
      (node (ref "LED_CH_B") (pin "A") (pinfunction "A_A") (pintype "passive"))
      (node (ref "R53") (pin "1") (pinfunction "1_1") (pintype "passive"))
    )
    (net (code "19") (name "Net-(LED_POWER-PadA)") (class "Default")
      (node (ref "LED_POWER") (pin "A") (pinfunction "A_A") (pintype "passive"))
      (node (ref "R60") (pin "1") (pinfunction "1_1") (pintype "passive"))
    )
    (net (code "20") (name "Net-(MULTI-E)") (class "Default")
      (node (ref "MULTI") (pin "3") (pinfunction "E_3") (pintype "passive"))
      (node (ref "R7") (pin "1") (pinfunction "1_1") (pintype "passive"))
    )
    (net (code "21") (name "Net-(Q1-D-Pad2)") (class "Default")
      (node (ref "Q1") (pin "2") (pinfunction "D_2") (pintype "passive"))
      (node (ref "Q1") (pin "4") (pinfunction "D_4") (pintype "passive"))
      (node (ref "TR1") (pin "4") (pinfunction "4_4") (pintype "passive"))
    )
    (net (code "22") (name "Net-(Q1-G)") (class "Default")
      (node (ref "Q1") (pin "1") (pinfunction "G_1") (pintype "passive"))
      (node (ref "R38") (pin "2") (pinfunction "2_2") (pintype "passive"))
    )
    (net (code "23") (name "Net-(Q2-D-Pad2)") (class "Default")
      (node (ref "Q2") (pin "2") (pinfunction "D_2") (pintype "passive"))
      (node (ref "Q2") (pin "4") (pinfunction "D_4") (pintype "passive"))
      (node (ref "TR1") (pin "6") (pinfunction "6_6") (pintype "passive"))
    )
    (net (code "24") (name "Net-(Q2-G)") (class "Default")
      (node (ref "Q2") (pin "1") (pinfunction "G_1") (pintype "passive"))
      (node (ref "R41") (pin "2") (pinfunction "2_2") (pintype "passive"))
    )
    (net (code "25") (name "Net-(Q3-D-Pad2)") (class "Default")
      (node (ref "Q3") (pin "2") (pinfunction "D_2") (pintype "passive"))
      (node (ref "Q3") (pin "4") (pinfunction "D_4") (pintype "passive"))
      (node (ref "TR1") (pin "5") (pinfunction "5_5") (pintype "passive"))
    )
    (net (code "26") (name "Net-(Q3-G)") (class "Default")
      (node (ref "C39") (pin "1") (pinfunction "1_1") (pintype "passive"))
      (node (ref "Q3") (pin "1") (pinfunction "G_1") (pintype "passive"))
      (node (ref "R39") (pin "2") (pinfunction "2_2") (pintype "passive"))
    )
    (net (code "27") (name "Net-(Q4-D-Pad2)") (class "Default")
      (node (ref "Q4") (pin "2") (pinfunction "D_2") (pintype "passive"))
      (node (ref "Q4") (pin "4") (pinfunction "D_4") (pintype "passive"))
      (node (ref "TR2") (pin "4") (pinfunction "4_4") (pintype "passive"))
    )
    (net (code "28") (name "Net-(Q4-G)") (class "Default")
      (node (ref "Q4") (pin "1") (pinfunction "G_1") (pintype "passive"))
      (node (ref "R49") (pin "2") (pinfunction "2_2") (pintype "passive"))
    )
    (net (code "29") (name "Net-(Q5-D-Pad2)") (class "Default")
      (node (ref "Q5") (pin "2") (pinfunction "D_2") (pintype "passive"))
      (node (ref "Q5") (pin "4") (pinfunction "D_4") (pintype "passive"))
      (node (ref "TR2") (pin "6") (pinfunction "6_6") (pintype "passive"))
    )
    (net (code "30") (name "Net-(Q5-G)") (class "Default")
      (node (ref "Q5") (pin "1") (pinfunction "G_1") (pintype "passive"))
      (node (ref "R52") (pin "2") (pinfunction "2_2") (pintype "passive"))
    )
    (net (code "31") (name "Net-(Q6-D-Pad2)") (class "Default")
      (node (ref "Q6") (pin "2") (pinfunction "D_2") (pintype "passive"))
      (node (ref "Q6") (pin "4") (pinfunction "D_4") (pintype "passive"))
      (node (ref "TR2") (pin "5") (pinfunction "5_5") (pintype "passive"))
    )
    (net (code "32") (name "Net-(Q6-G)") (class "Default")
      (node (ref "C40") (pin "1") (pinfunction "1_1") (pintype "passive"))
      (node (ref "Q6") (pin "1") (pinfunction "G_1") (pintype "passive"))
      (node (ref "R50") (pin "2") (pinfunction "2_2") (pintype "passive"))
    )
    (net (code "33") (name "Net-(Q7-PadB)") (class "Default")
      (node (ref "Q7") (pin "B") (pinfunction "B_B") (pintype "passive"))
      (node (ref "R56") (pin "1") (pinfunction "1_1") (pintype "passive"))
    )
    (net (code "34") (name "Net-(Q7-PadC)") (class "Default")
      (node (ref "Q7") (pin "C") (pinfunction "C_C") (pintype "passive"))
      (node (ref "Q8") (pin "B") (pinfunction "B_B") (pintype "passive"))
      (node (ref "R57") (pin "2") (pinfunction "2_2") (pintype "passive"))
    )
    (net (code "35") (name "Net-(U1-(ADC2)PA2)") (class "Default")
      (node (ref "R4") (pin "2") (pinfunction "2_2") (pintype "passive"))
      (node (ref "U1") (pin "35") (pinfunction "(ADC2)PA2_35") (pintype "bidirectional"))
    )
    (net (code "36") (name "Net-(U1-(ADC3)PA3)") (class "Default")
      (node (ref "R5") (pin "1") (pinfunction "1_1") (pintype "passive"))
      (node (ref "R6") (pin "2") (pinfunction "2_2") (pintype "passive"))
      (node (ref "U1") (pin "34") (pinfunction "(ADC3)PA3_34") (pintype "bidirectional"))
    )
    (net (code "37") (name "Net-(U1-(ADC6)PA6)") (class "Default")
      (node (ref "R2") (pin "1") (pinfunction "1_1") (pintype "passive"))
      (node (ref "U1") (pin "31") (pinfunction "(ADC6)PA6_31") (pintype "bidirectional"))
    )
    (net (code "38") (name "Net-(U1-(ADC7)PA7)") (class "Default")
      (node (ref "R1") (pin "1") (pinfunction "1_1") (pintype "passive"))
      (node (ref "U1") (pin "30") (pinfunction "(ADC7)PA7_30") (pintype "bidirectional"))
    )
    (net (code "39") (name "Net-(U1-(RXD)PD0)") (class "Default")
      (node (ref "U1") (pin "9") (pinfunction "(RXD)PD0_9") (pintype "bidirectional"))
      (node (ref "UART") (pin "2") (pinfunction "2_2") (pintype "passive"))
    )
    (net (code "40") (name "Net-(U1-(TXD)PD1)") (class "Default")
      (node (ref "U1") (pin "10") (pinfunction "(TXD)PD1_10") (pintype "bidirectional"))
      (node (ref "UART") (pin "1") (pinfunction "1_1") (pintype "passive"))
    )
    (net (code "41") (name "Net-(U1-XTAL1)") (class "Default")
      (node (ref "C16") (pin "1") (pinfunction "1_1") (pintype "passive"))
      (node (ref "U1") (pin "8") (pinfunction "XTAL1_8") (pintype "bidirectional"))
      (node (ref "Y1") (pin "2") (pinfunction "2_2") (pintype "passive"))
    )
    (net (code "42") (name "Net-(U1-XTAL2)") (class "Default")
      (node (ref "C15") (pin "1") (pinfunction "1_1") (pintype "passive"))
      (node (ref "U1") (pin "7") (pinfunction "XTAL2_7") (pintype "bidirectional"))
      (node (ref "Y1") (pin "1") (pinfunction "1_1") (pintype "passive"))
    )
    (net (code "43") (name "Net-(U3A-A)") (class "Default")
      (node (ref "C7") (pin "1") (pinfunction "1_1") (pintype "passive"))
      (node (ref "MENU") (pin "1") (pinfunction "S_1") (pintype "passive"))
      (node (ref "MENU") (pin "2") (pinfunction "S_2") (pintype "passive"))
      (node (ref "R11") (pin "2") (pinfunction "2_2") (pintype "passive"))
      (node (ref "U3") (pin "1") (pinfunction "A_1") (pintype "tri_state"))
    )
    (net (code "44") (name "Net-(U3B-A)") (class "Default")
      (node (ref "C5") (pin "1") (pinfunction "1_1") (pintype "passive"))
      (node (ref "R10") (pin "2") (pinfunction "2_2") (pintype "passive"))
      (node (ref "RIGHT") (pin "1") (pinfunction "S_1") (pintype "passive"))
      (node (ref "RIGHT") (pin "2") (pinfunction "S_2") (pintype "passive"))
      (node (ref "U3") (pin "4") (pinfunction "A_4") (pintype "tri_state"))
    )
    (net (code "45") (name "Net-(U3C-A)") (class "Default")
      (node (ref "C4") (pin "1") (pinfunction "1_1") (pintype "passive"))
      (node (ref "OK") (pin "1") (pinfunction "S_1") (pintype "passive"))
      (node (ref "OK") (pin "2") (pinfunction "S_2") (pintype "passive"))
      (node (ref "R9") (pin "2") (pinfunction "2_2") (pintype "passive"))
      (node (ref "U3") (pin "8") (pinfunction "A_8") (pintype "tri_state"))
    )
    (net (code "46") (name "Net-(U3D-A)") (class "Default")
      (node (ref "C3") (pin "1") (pinfunction "1_1") (pintype "passive"))
      (node (ref "LEFT") (pin "1") (pinfunction "S_1") (pintype "passive"))
      (node (ref "LEFT") (pin "2") (pinfunction "S_2") (pintype "passive"))
      (node (ref "R8") (pin "2") (pinfunction "2_2") (pintype "passive"))
      (node (ref "U3") (pin "11") (pinfunction "A_11") (pintype "tri_state"))
    )
    (net (code "47") (name "Net-(U8B-VOUT_A)") (class "Default")
      (node (ref "R42") (pin "1") (pinfunction "1_1") (pintype "passive"))
      (node (ref "U8B") (pin "8") (pinfunction "VOUT_A_8") (pintype "output"))
    )
    (net (code "48") (name "Net-(U8B-VOUT_B)") (class "Default")
      (node (ref "R31") (pin "1") (pinfunction "1_1") (pintype "passive"))
      (node (ref "U8B") (pin "5") (pinfunction "VOUT_B_5") (pintype "output"))
    )
    (net (code "49") (name "Net-(U10A-+IN)") (class "Default")
      (node (ref "R31") (pin "2") (pinfunction "2_2") (pintype "passive"))
      (node (ref "R32") (pin "1") (pinfunction "1_1") (pintype "passive"))
      (node (ref "R33") (pin "2") (pinfunction "2_2") (pintype "passive"))
      (node (ref "U10") (pin "3") (pinfunction "+IN_3") (pintype "input"))
    )
    (net (code "50") (name "Net-(U10A--IN)") (class "Default")
      (node (ref "R34") (pin "1") (pinfunction "1_1") (pintype "passive"))
      (node (ref "R35") (pin "2") (pinfunction "2_2") (pintype "passive"))
      (node (ref "R36") (pin "1") (pinfunction "1_1") (pintype "passive"))
      (node (ref "U10") (pin "2") (pinfunction "-IN_2") (pintype "input"))
    )
    (net (code "51") (name "Net-(U10A-OUT)") (class "Default")
      (node (ref "R36") (pin "2") (pinfunction "2_2") (pintype "passive"))
      (node (ref "R39") (pin "1") (pinfunction "1_1") (pintype "passive"))
      (node (ref "U10") (pin "1") (pinfunction "OUT_1") (pintype "output"))
    )
    (net (code "52") (name "Net-(U10B-+IN)") (class "Default")
      (node (ref "R42") (pin "2") (pinfunction "2_2") (pintype "passive"))
      (node (ref "R43") (pin "1") (pinfunction "1_1") (pintype "passive"))
      (node (ref "R44") (pin "2") (pinfunction "2_2") (pintype "passive"))
      (node (ref "U10") (pin "5") (pinfunction "+IN_5") (pintype "input"))
    )
    (net (code "53") (name "Net-(U10B--IN)") (class "Default")
      (node (ref "R45") (pin "1") (pinfunction "1_1") (pintype "passive"))
      (node (ref "R46") (pin "2") (pinfunction "2_2") (pintype "passive"))
      (node (ref "R47") (pin "1") (pinfunction "1_1") (pintype "passive"))
      (node (ref "U10") (pin "6") (pinfunction "-IN_6") (pintype "input"))
    )
    (net (code "54") (name "Net-(U10B-OUT)") (class "Default")
      (node (ref "R47") (pin "2") (pinfunction "2_2") (pintype "passive"))
      (node (ref "R50") (pin "1") (pinfunction "1_1") (pintype "passive"))
      (node (ref "U10") (pin "7") (pinfunction "OUT_7") (pintype "output"))
    )
    (net (code "55") (name "PA0") (class "Default")
      (node (ref "Q1") (pin "3") (pinfunction "S_3") (pintype "passive"))
      (node (ref "Q2") (pin "3") (pinfunction "S_3") (pintype "passive"))
      (node (ref "Q4") (pin "3") (pinfunction "S_3") (pintype "passive"))
      (node (ref "Q5") (pin "3") (pinfunction "S_3") (pintype "passive"))
      (node (ref "R30") (pin "2") (pinfunction "2_2") (pintype "passive"))
      (node (ref "R30_2") (pin "2") (pinfunction "2_2") (pintype "passive"))
      (node (ref "U1") (pin "37") (pinfunction "(ADC0)PA0_37") (pintype "bidirectional"))
    )
    (net (code "56") (name "PA1") (class "Default")
      (node (ref "MULTI") (pin "2") (pinfunction "S_2") (pintype "passive"))
      (node (ref "U1") (pin "36") (pinfunction "(ADC1)PA1_36") (pintype "bidirectional"))
    )
    (net (code "57") (name "PA4") (class "Default")
      (node (ref "LEVEL_A") (pin "2") (pinfunction "S_2") (pintype "passive"))
      (node (ref "U1") (pin "33") (pinfunction "(ADC4)PA4_33") (pintype "bidirectional"))
    )
    (net (code "58") (name "PA5") (class "Default")
      (node (ref "LEVEL_B") (pin "2") (pinfunction "S_2") (pintype "passive"))
      (node (ref "U1") (pin "32") (pinfunction "(ADC5)PA5_32") (pintype "bidirectional"))
    )
    (net (code "59") (name "PB0") (class "Default")
      (node (ref "R48") (pin "2") (pinfunction "2_2") (pintype "passive"))
      (node (ref "R49") (pin "1") (pinfunction "1_1") (pintype "passive"))
      (node (ref "U1") (pin "40") (pinfunction "(T0/XCK)PB0_40") (pintype "bidirectional"))
    )
    (net (code "60") (name "PB1") (class "Default")
      (node (ref "R51") (pin "2") (pinfunction "2_2") (pintype "passive"))
      (node (ref "R52") (pin "1") (pinfunction "1_1") (pintype "passive"))
      (node (ref "U1") (pin "41") (pinfunction "(T1)PB1_41") (pintype "bidirectional"))
    )
    (net (code "61") (name "PB2") (class "Default")
      (node (ref "R37") (pin "2") (pinfunction "2_2") (pintype "passive"))
      (node (ref "R38") (pin "1") (pinfunction "1_1") (pintype "passive"))
      (node (ref "U1") (pin "42") (pinfunction "(AIN0/INT2)PB2_42") (pintype "bidirectional"))
    )
    (net (code "62") (name "PB3") (class "Default")
      (node (ref "R40") (pin "2") (pinfunction "2_2") (pintype "passive"))
      (node (ref "R41") (pin "1") (pinfunction "1_1") (pintype "passive"))
      (node (ref "U1") (pin "43") (pinfunction "(AIN1/OC0)PB3_43") (pintype "bidirectional"))
    )
    (net (code "63") (name "PB5") (class "Default")
      (node (ref "ISP1") (pin "4") (pinfunction "MOSI_4") (pintype "output"))
      (node (ref "U1") (pin "1") (pinfunction "(MOSI)PB5_1") (pintype "bidirectional"))
      (node (ref "U8B") (pin "3") (pinfunction "D_IN_3") (pintype "input"))
    )
    (net (code "64") (name "PB6") (class "Default")
      (node (ref "ISP1") (pin "1") (pinfunction "MISO_1") (pintype "input"))
      (node (ref "U1") (pin "2") (pinfunction "(MISO)PB6_2") (pintype "bidirectional"))
    )
    (net (code "65") (name "PB7") (class "Default")
      (node (ref "ISP1") (pin "3") (pinfunction "SCK_3") (pintype "output"))
      (node (ref "U1") (pin "3") (pinfunction "(SCK)PB7_3") (pintype "bidirectional"))
      (node (ref "U8B") (pin "2") (pinfunction "SCK_2") (pintype "input"))
    )
    (net (code "66") (name "PC0") (class "Default")
      (node (ref "U1") (pin "19") (pinfunction "PC0(SCL)_19") (pintype "bidirectional"))
      (node (ref "U3") (pin "12") (pinfunction "C_12") (pintype "input"))
      (node (ref "U3") (pin "13") (pinfunction "C_13") (pintype "input"))
      (node (ref "U3") (pin "5") (pinfunction "C_5") (pintype "input"))
      (node (ref "U3") (pin "6") (pinfunction "C_6") (pintype "input"))
    )
    (net (code "67") (name "PC1") (class "Default")
      (node (ref "LCD1") (pin "5") (pinfunction "RW_5") (pintype "input"))
      (node (ref "U1") (pin "20") (pinfunction "PC1(SDA)_20") (pintype "bidirectional"))
    )
    (net (code "68") (name "PC2") (class "Default")
      (node (ref "LCD1") (pin "6") (pinfunction "E_6") (pintype "input"))
      (node (ref "U1") (pin "21") (pinfunction "(TCK)PC2_21") (pintype "bidirectional"))
    )
    (net (code "69") (name "PC3") (class "Default")
      (node (ref "LCD1") (pin "4") (pinfunction "RS_4") (pintype "input"))
      (node (ref "U1") (pin "22") (pinfunction "(TMS)PC3_22") (pintype "bidirectional"))
    )
    (net (code "70") (name "PC4") (class "Default")
      (node (ref "LCD1") (pin "11") (pinfunction "DB4_11") (pintype "bidirectional"))
      (node (ref "U1") (pin "23") (pinfunction "(TDO)PC4_23") (pintype "bidirectional"))
      (node (ref "U3") (pin "10") (pinfunction "B_10") (pintype "tri_state"))
    )
    (net (code "71") (name "PC5") (class "Default")
      (node (ref "LCD1") (pin "12") (pinfunction "DB5_12") (pintype "bidirectional"))
      (node (ref "U1") (pin "24") (pinfunction "(TDI)PC5_24") (pintype "bidirectional"))
      (node (ref "U3") (pin "9") (pinfunction "B_9") (pintype "tri_state"))
    )
    (net (code "72") (name "PC6") (class "Default")
      (node (ref "LCD1") (pin "13") (pinfunction "DB6_13") (pintype "bidirectional"))
      (node (ref "U1") (pin "25") (pinfunction "(TOSC1)PC6_25") (pintype "bidirectional"))
      (node (ref "U3") (pin "3") (pinfunction "B_3") (pintype "tri_state"))
    )
    (net (code "73") (name "PC7") (class "Default")
      (node (ref "LCD1") (pin "14") (pinfunction "DB7_14") (pintype "bidirectional"))
      (node (ref "U1") (pin "26") (pinfunction "(TOSC2)PC7_26") (pintype "bidirectional"))
      (node (ref "U3") (pin "2") (pinfunction "B_2") (pintype "tri_state"))
    )
    (net (code "74") (name "PD5") (class "Default")
      (node (ref "LED_CH_B") (pin "K") (pinfunction "C_K") (pintype "passive"))
      (node (ref "U1") (pin "14") (pinfunction "(OC1A)PD5_14") (pintype "bidirectional"))
    )
    (net (code "75") (name "PD6") (class "Default")
      (node (ref "LED_CH_A") (pin "K") (pinfunction "C_K") (pintype "passive"))
      (node (ref "U1") (pin "15") (pinfunction "(ICP)PD6_15") (pintype "bidirectional"))
    )
    (net (code "76") (name "PD7") (class "Default")
      (node (ref "R56") (pin "2") (pinfunction "2_2") (pintype "passive"))
      (node (ref "U1") (pin "16") (pinfunction "(OC2)PD7_16") (pintype "bidirectional"))
    )
    (net (code "77") (name "RESET") (class "Default")
      (node (ref "C8") (pin "1") (pinfunction "1_1") (pintype "passive"))
      (node (ref "ISP1") (pin "5") (pinfunction "RST_5") (pintype "output"))
      (node (ref "R3") (pin "1") (pinfunction "1_1") (pintype "passive"))
      (node (ref "U1") (pin "4") (pinfunction "RESET_4") (pintype "input"))
    )
    (net (code "78") (name "unconnected-(CHAN_A-Pad2)") (class "Default")
      (node (ref "CHAN_A") (pin "2") (pinfunction "2_2") (pintype "bidirectional"))
    )
    (net (code "79") (name "unconnected-(CHAN_B-Pad2)") (class "Default")
      (node (ref "CHAN_B") (pin "2") (pinfunction "2_2") (pintype "bidirectional"))
    )
    (net (code "80") (name "unconnected-(DC_IN-SLEEVE_SHUNT-Pad2)") (class "Default")
      (node (ref "DC_IN") (pin "2") (pinfunction "SLEEVE_SHUNT_2") (pintype "bidirectional"))
    )
    (net (code "81") (name "unconnected-(IC1-~{ON{slash}OFF}-Pad5)") (class "Default")
      (node (ref "IC1") (pin "5") (pinfunction "~{ON/OFF}_5") (pintype "input"))
    )
    (net (code "82") (name "unconnected-(LCD1-DB0-Pad7)") (class "Default")
      (node (ref "LCD1") (pin "7") (pinfunction "DB0_7") (pintype "bidirectional"))
    )
    (net (code "83") (name "unconnected-(LCD1-DB1-Pad8)") (class "Default")
      (node (ref "LCD1") (pin "8") (pinfunction "DB1_8") (pintype "bidirectional"))
    )
    (net (code "84") (name "unconnected-(LCD1-DB2-Pad9)") (class "Default")
      (node (ref "LCD1") (pin "9") (pinfunction "DB2_9") (pintype "bidirectional"))
    )
    (net (code "85") (name "unconnected-(LCD1-DB3-Pad10)") (class "Default")
      (node (ref "LCD1") (pin "10") (pinfunction "DB3_10") (pintype "bidirectional"))
    )
    (net (code "86") (name "unconnected-(TR1-Pad2)") (class "Default")
      (node (ref "TR1") (pin "2") (pinfunction "2_2") (pintype "passive"))
    )
    (net (code "87") (name "unconnected-(TR2-Pad2)") (class "Default")
      (node (ref "TR2") (pin "2") (pinfunction "2_2") (pintype "passive"))
    )
    (net (code "88") (name "unconnected-(U1-(INT0)PD2-Pad11)") (class "Default")
      (node (ref "U1") (pin "11") (pinfunction "(INT0)PD2_11") (pintype "bidirectional"))
    )
    (net (code "89") (name "unconnected-(U1-(INT1)PD3-Pad12)") (class "Default")
      (node (ref "U1") (pin "12") (pinfunction "(INT1)PD3_12") (pintype "bidirectional"))
    )
    (net (code "90") (name "unconnected-(U1-(SS)PB4-Pad44)") (class "Default")
      (node (ref "U1") (pin "44") (pinfunction "(SS)PB4_44") (pintype "bidirectional"))
    )
    (net (code "91") (name "~{CS}") (class "Default")
      (node (ref "U1") (pin "13") (pinfunction "(OC1B)PD4_13") (pintype "bidirectional"))
      (node (ref "U8B") (pin "1") (pinfunction "CS/LD_1") (pintype "input"))
    )
  )
)
